# module_special_reg.net
KiCad netlist of a schematic drawn in EAGLE
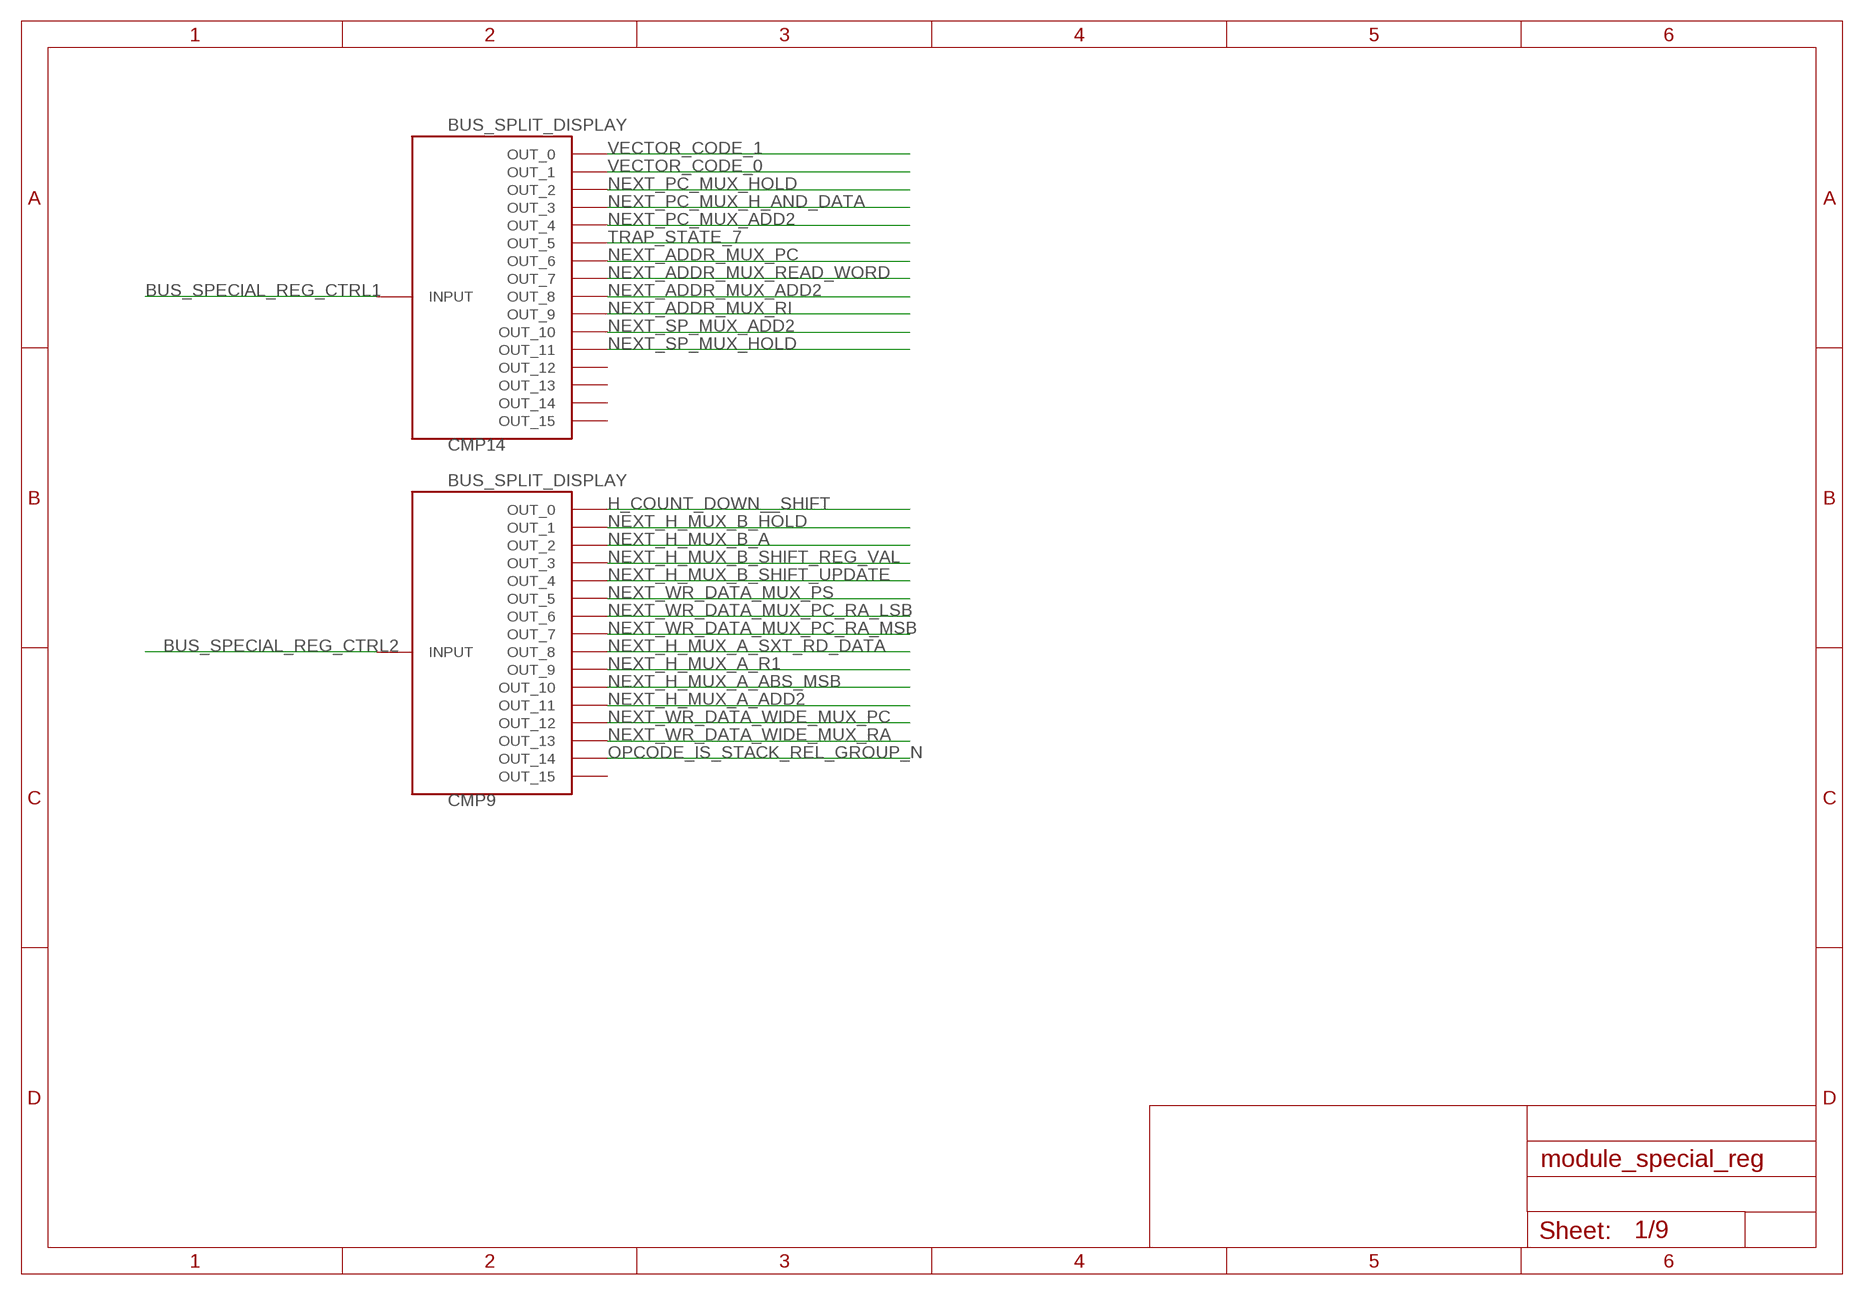
[diagram p0: schematic, sheet 1]
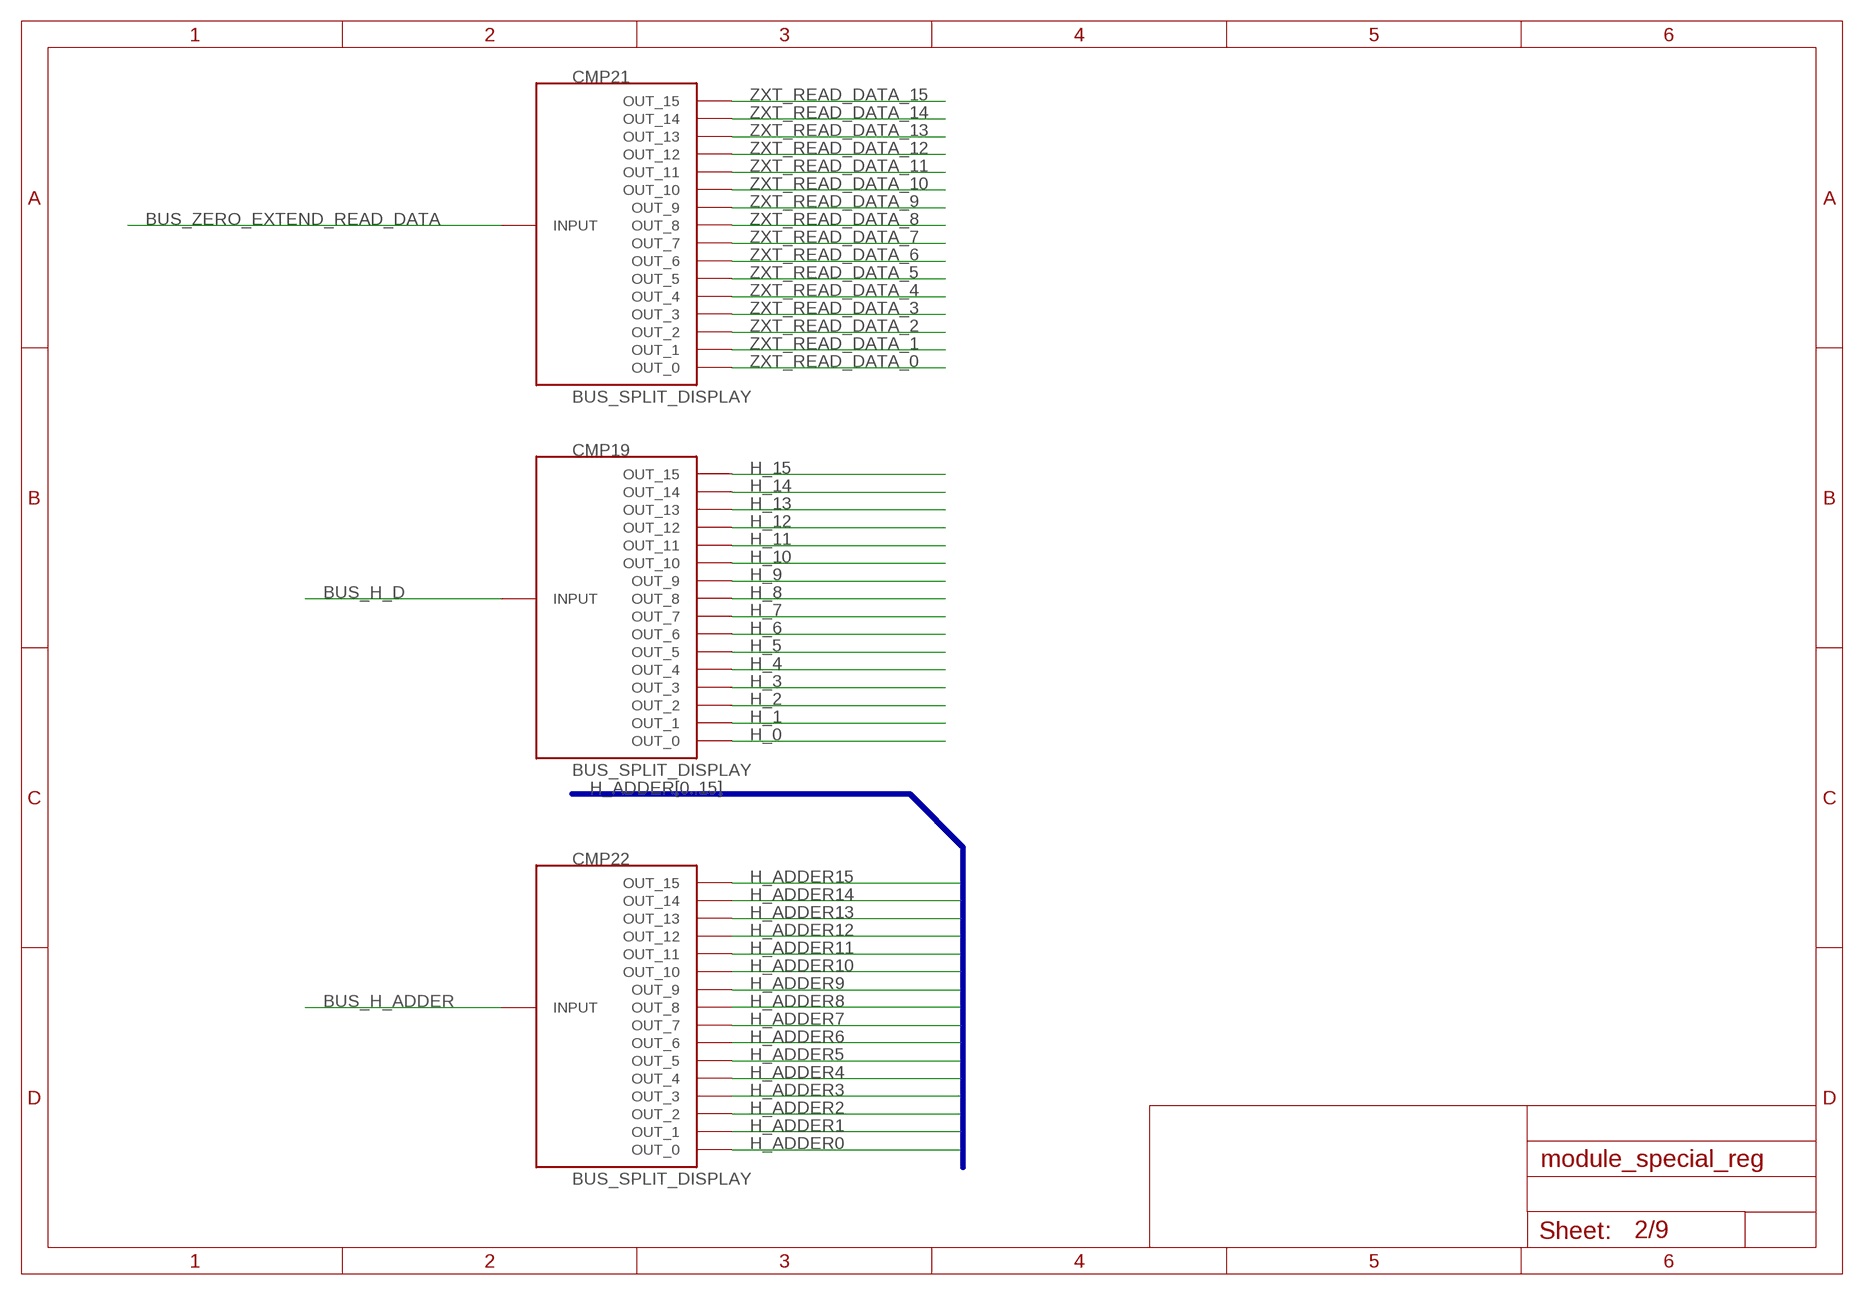
[diagram p1: schematic, sheet 2]
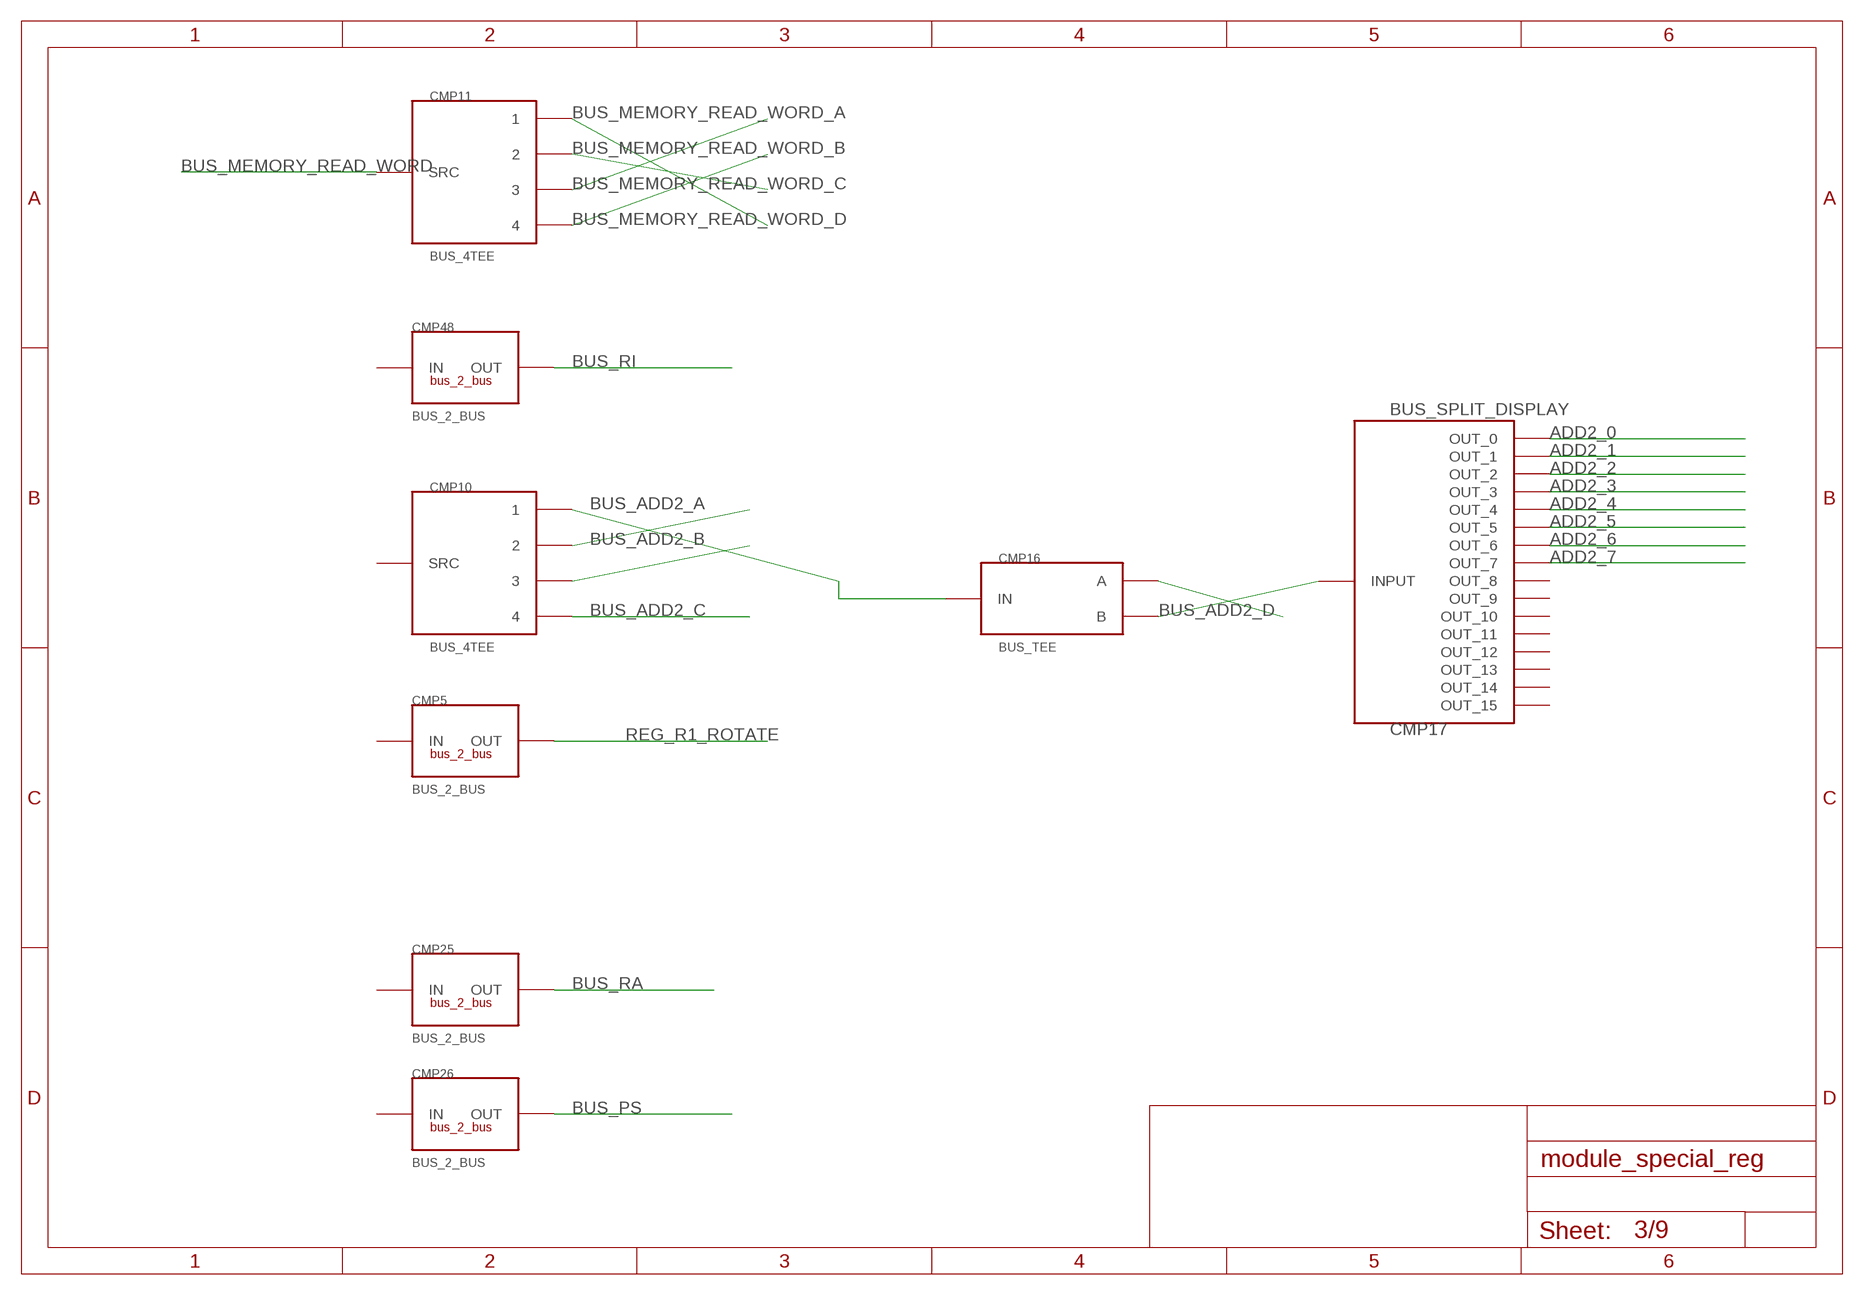
[diagram p2: schematic, sheet 3]
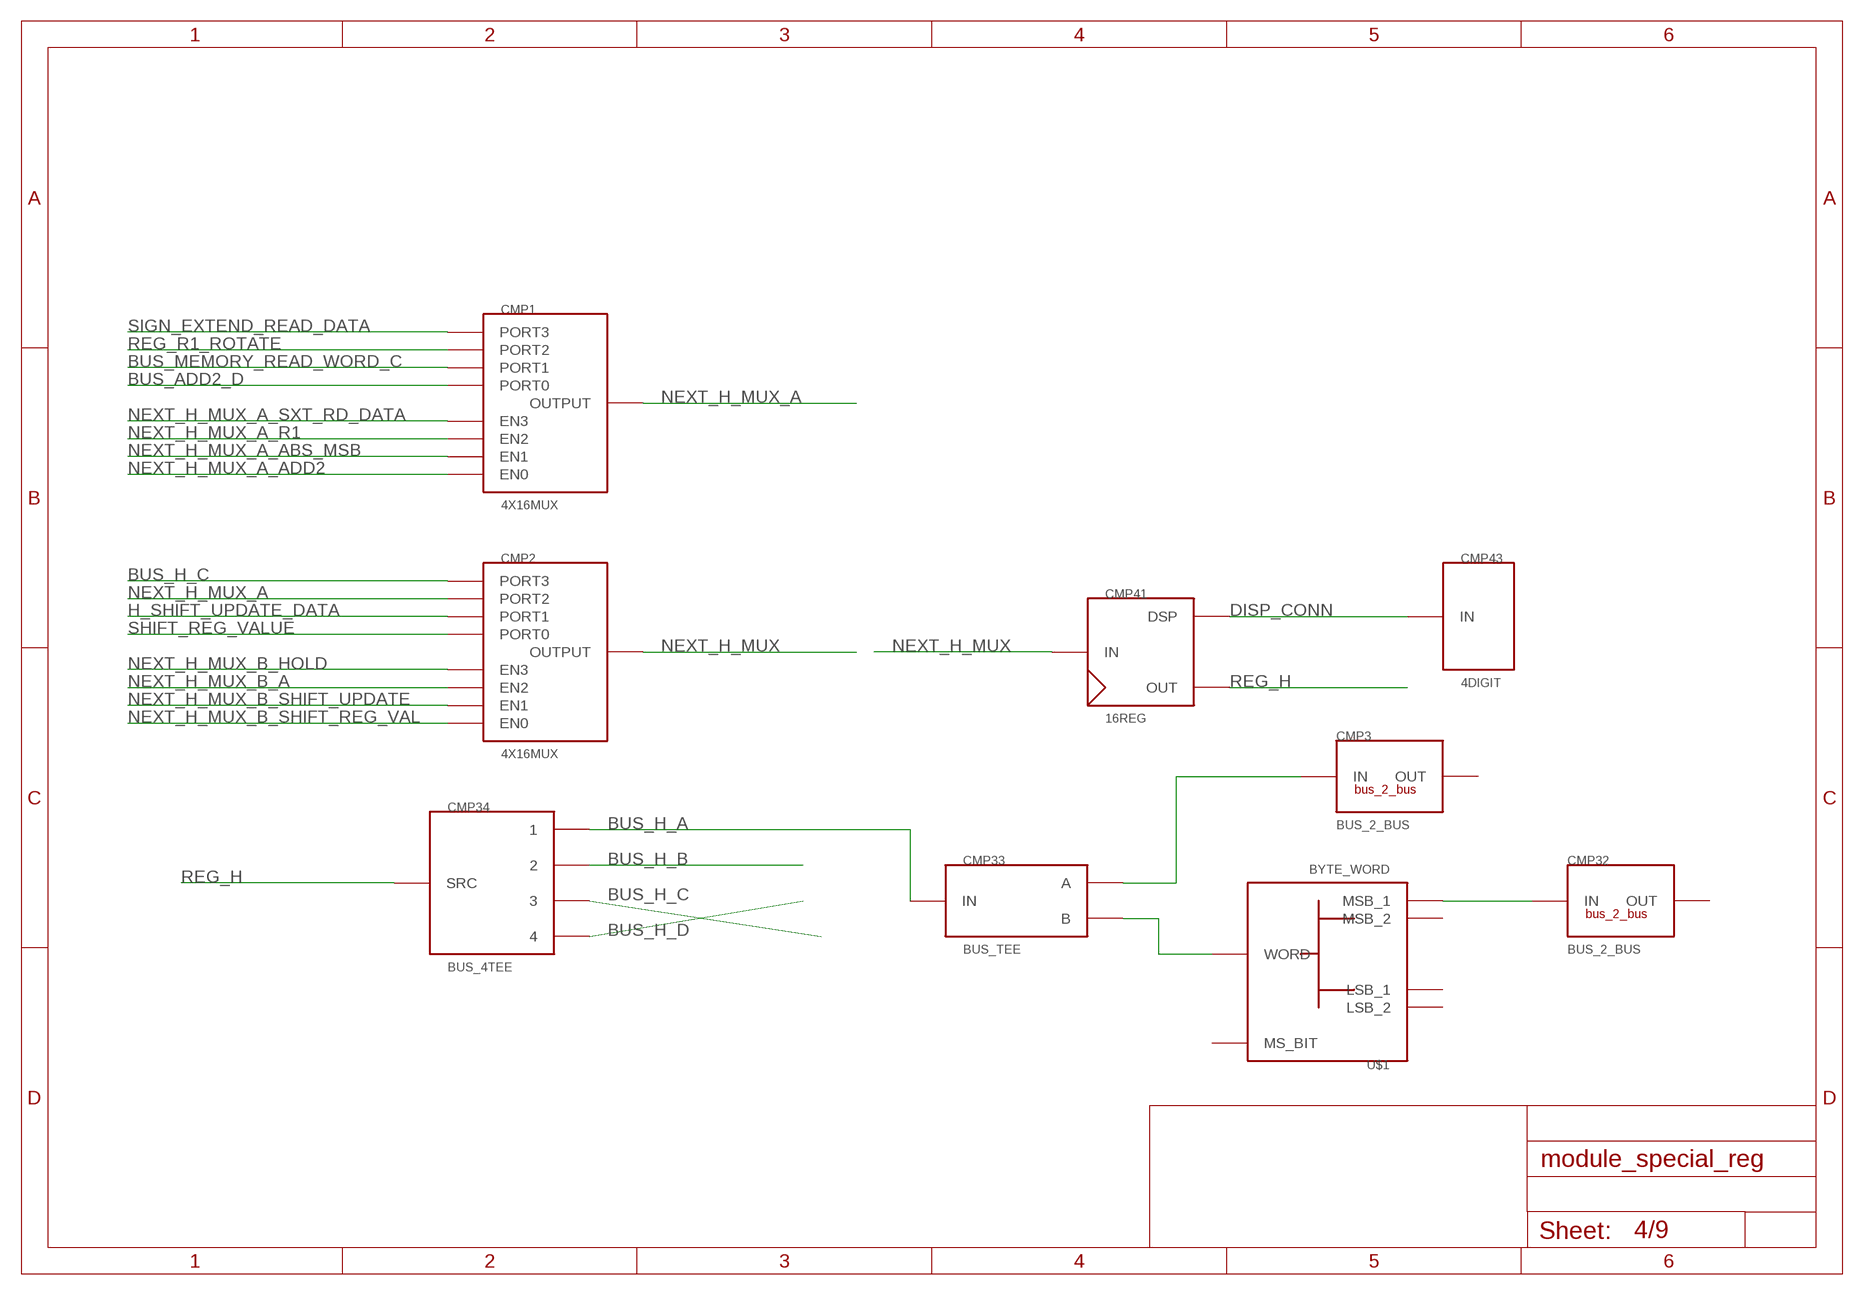
[diagram p3: schematic, sheet 4]
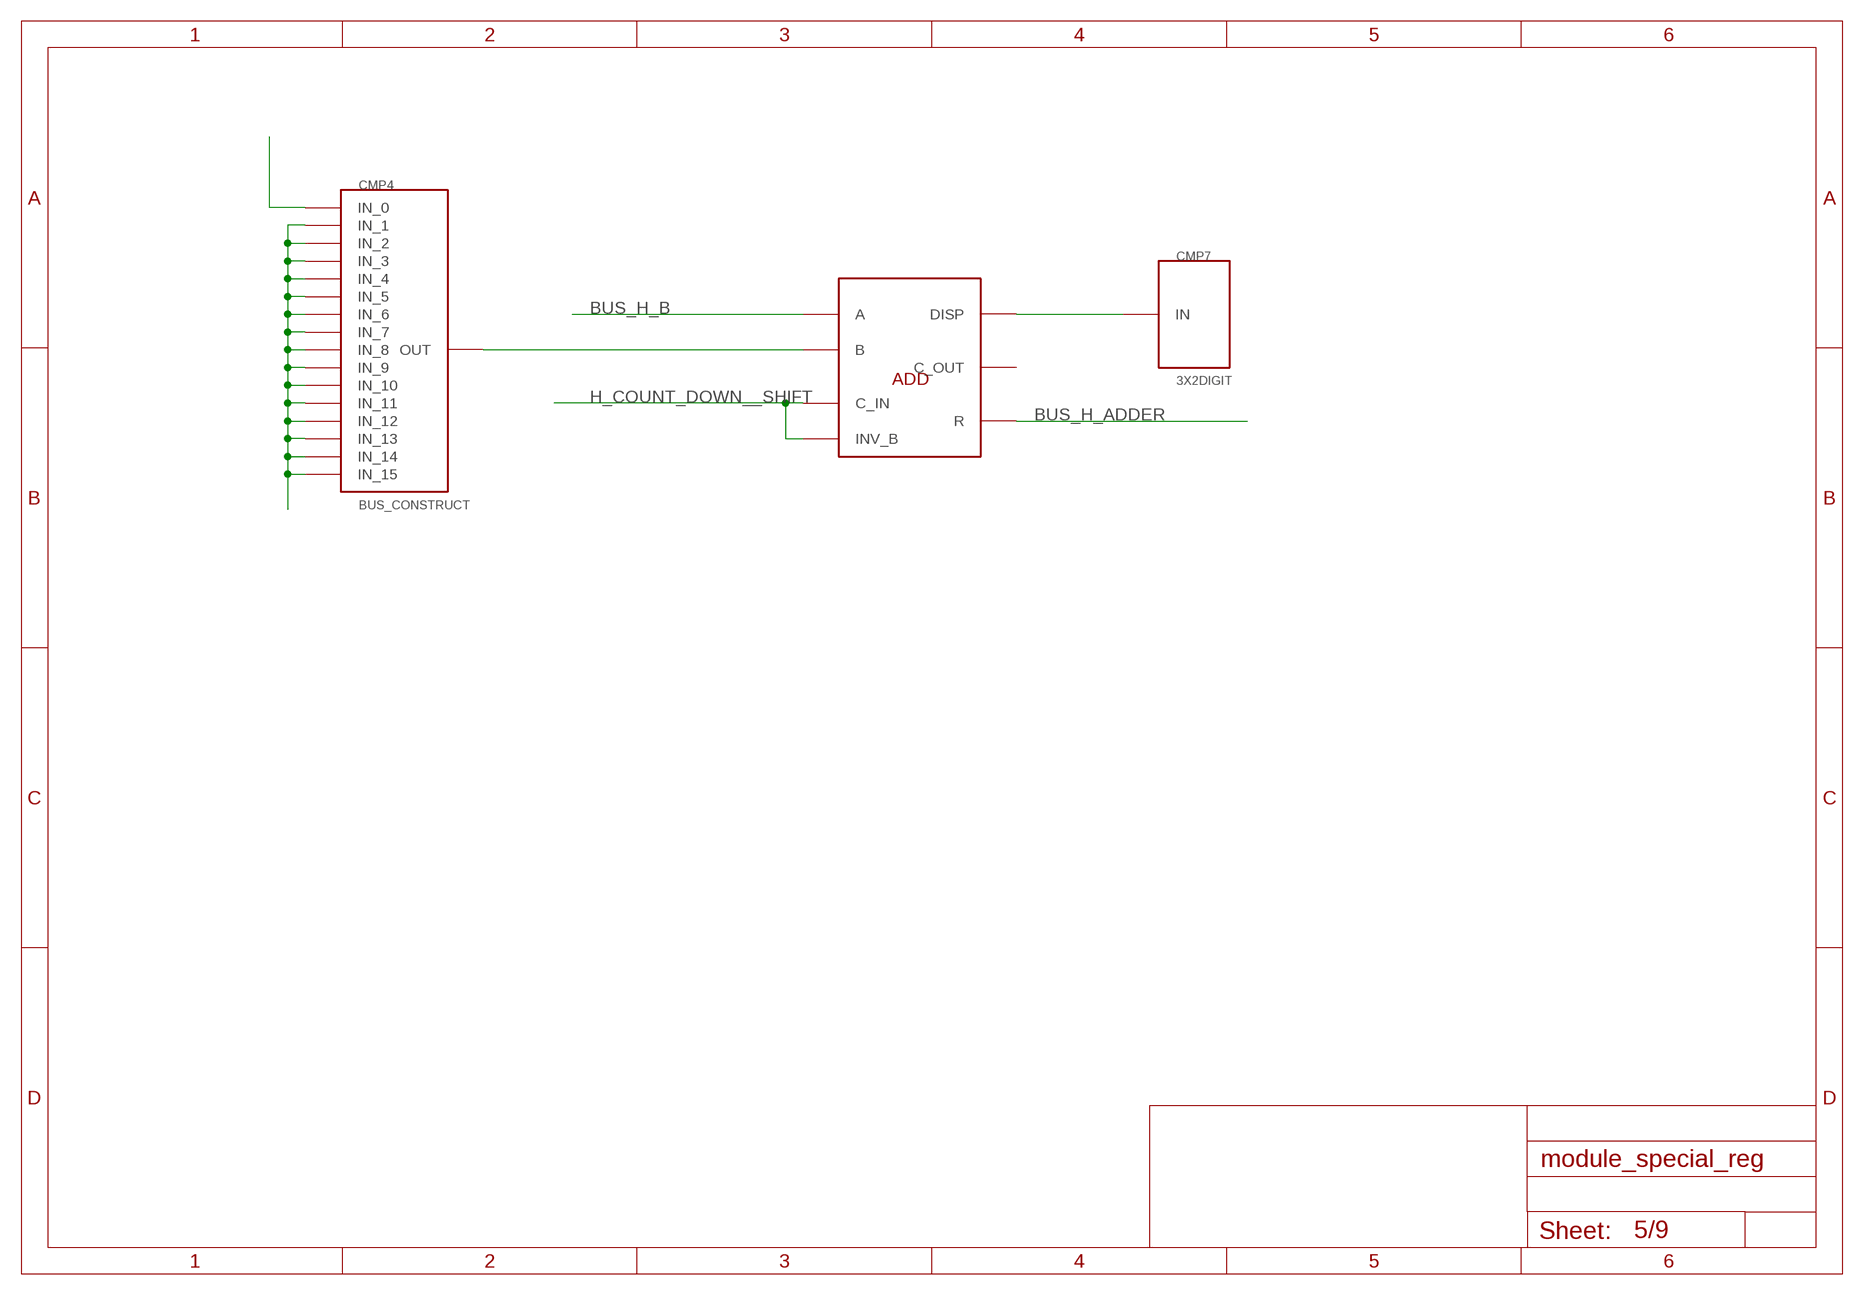
[diagram p4: schematic, sheet 5]
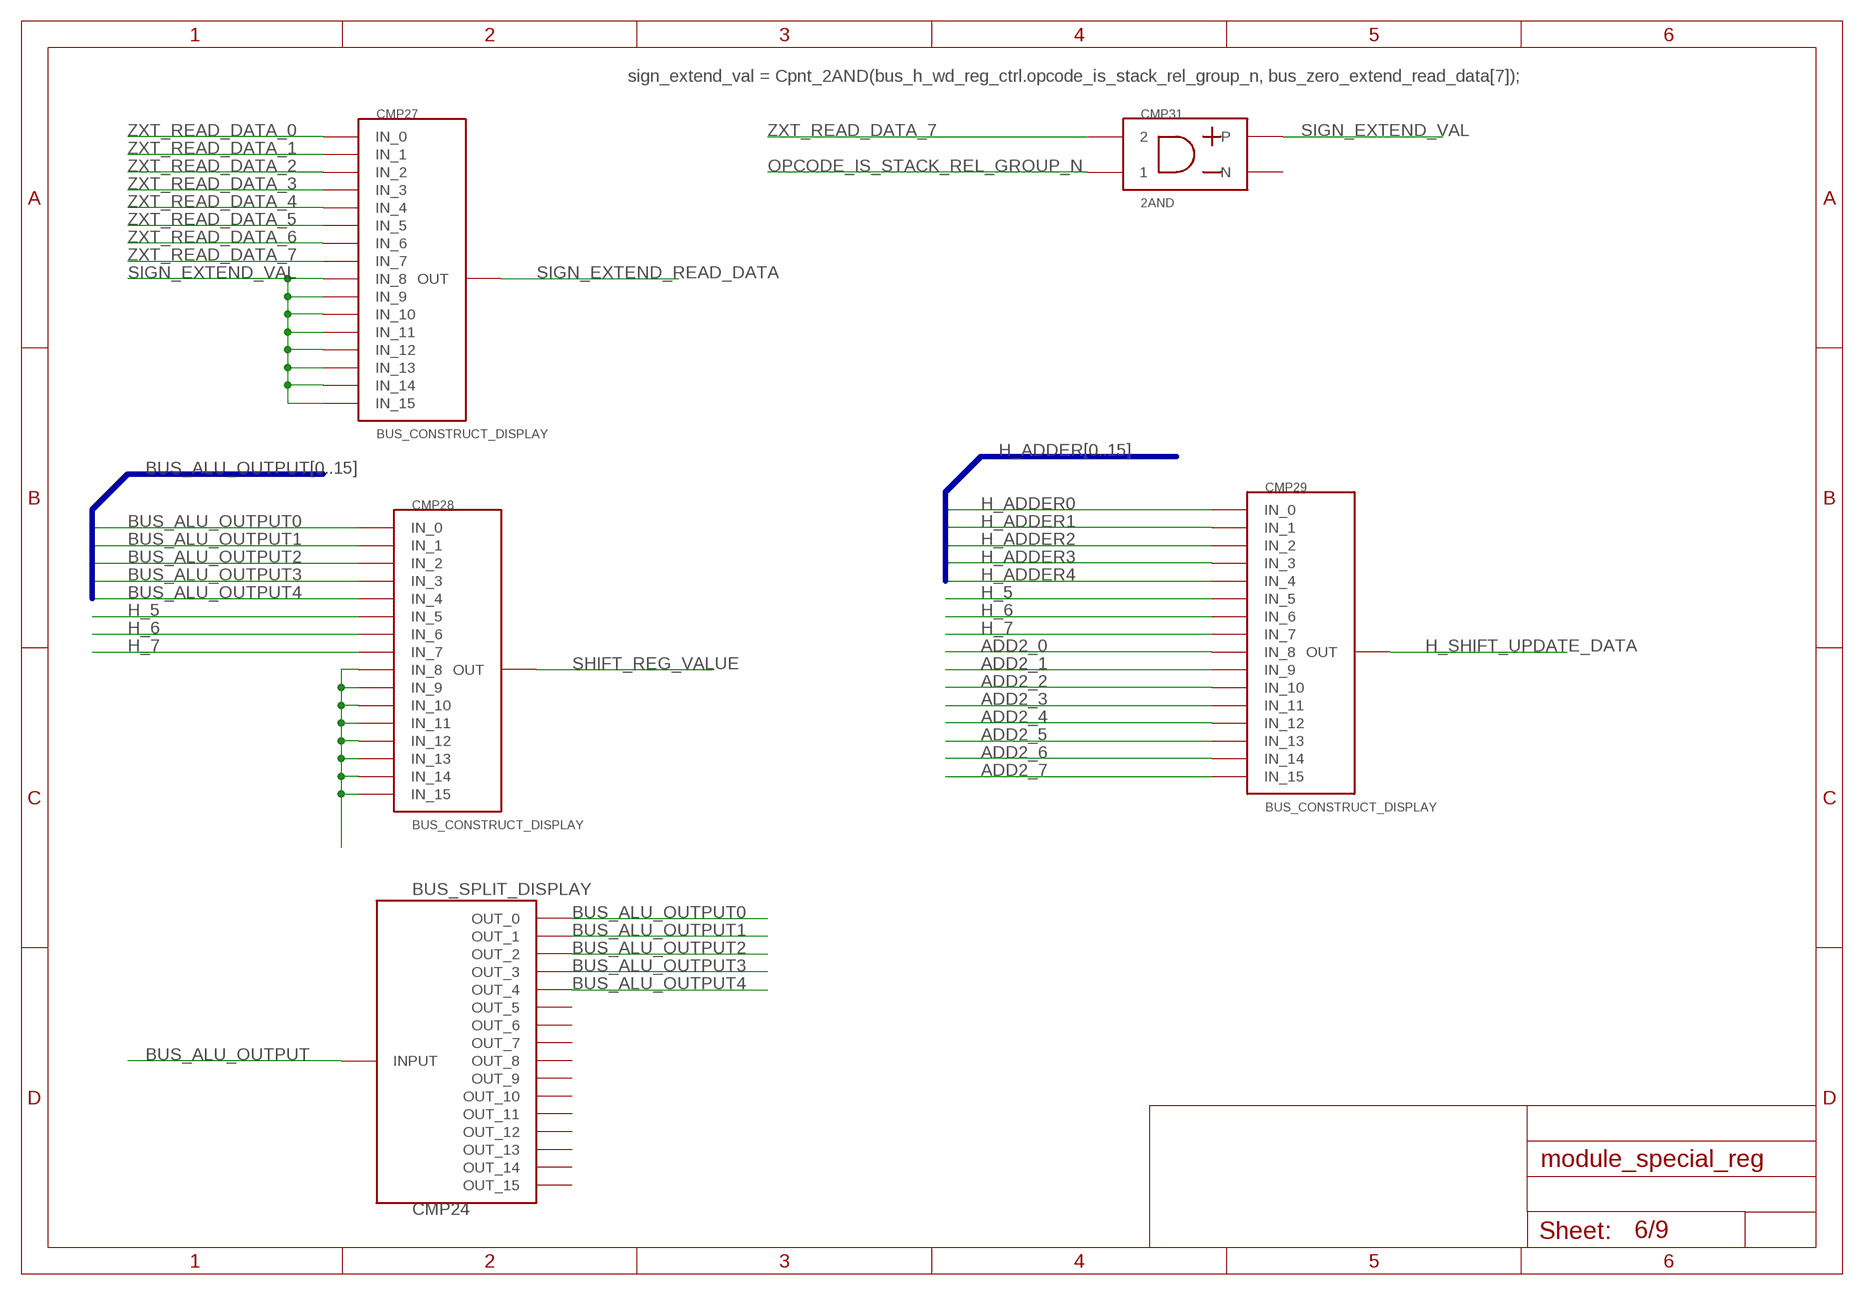
[diagram p5: schematic, sheet 6]
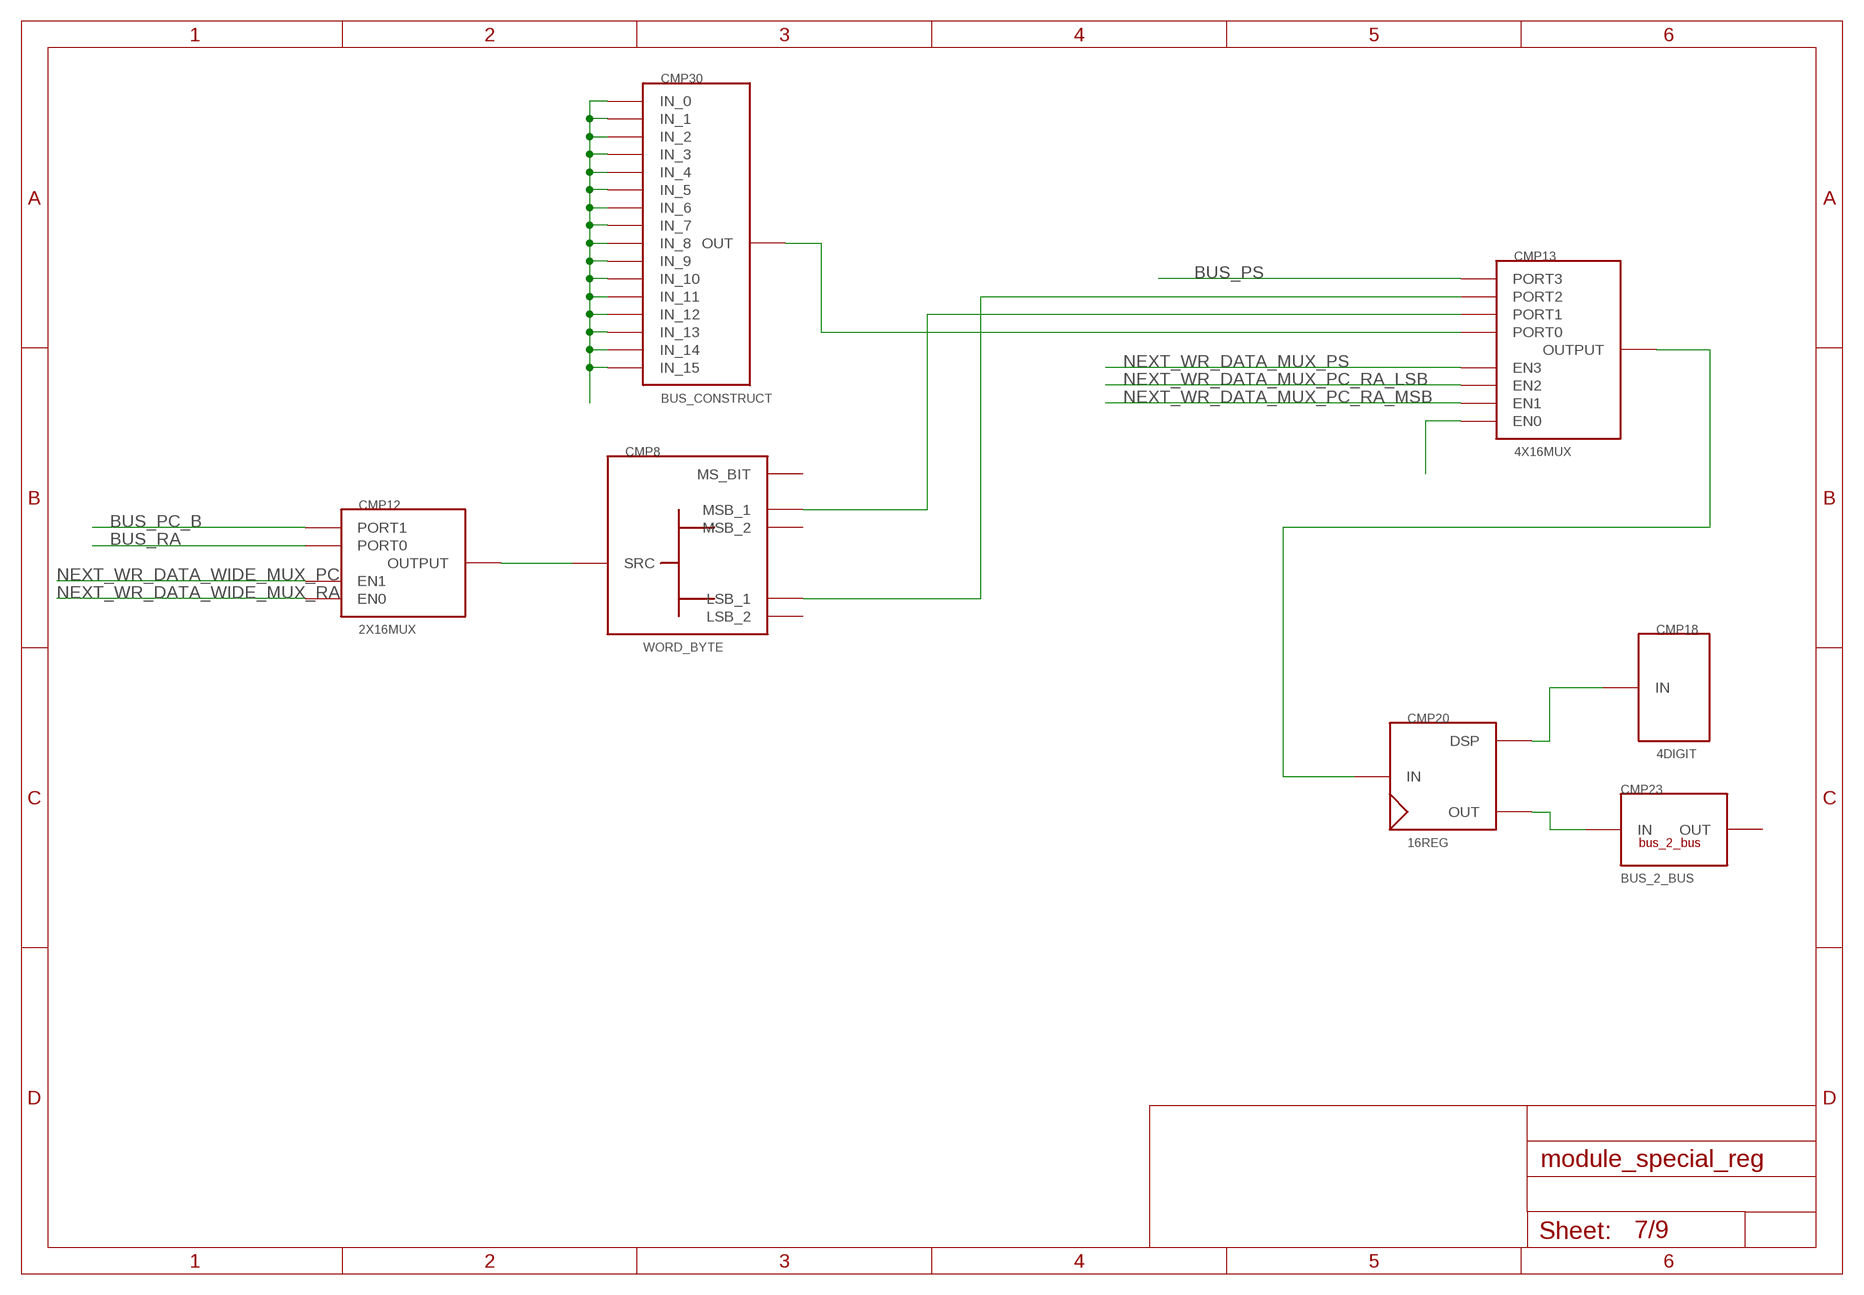
[diagram p6: schematic, sheet 7]
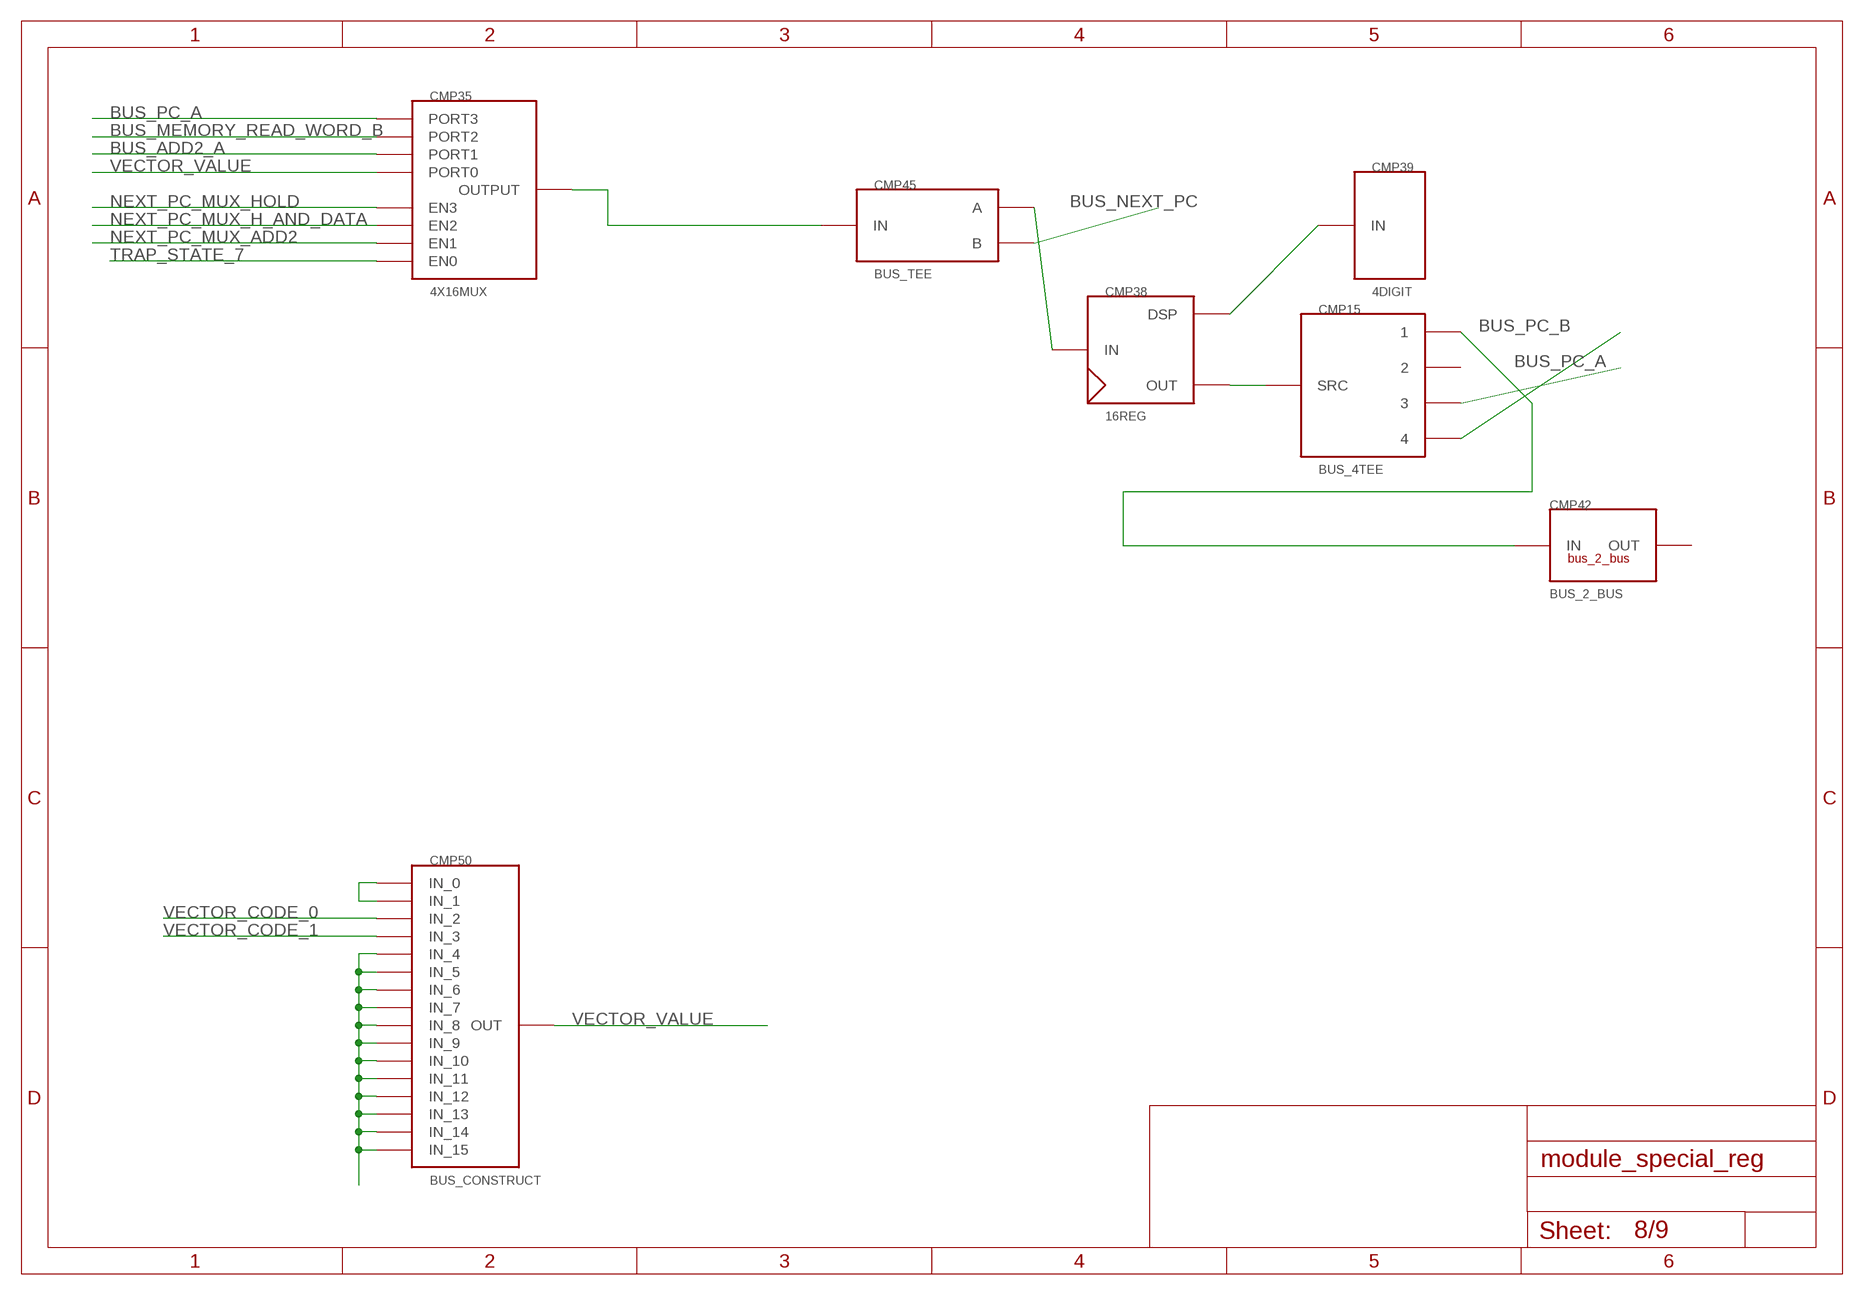
[diagram p7: schematic, sheet 8]
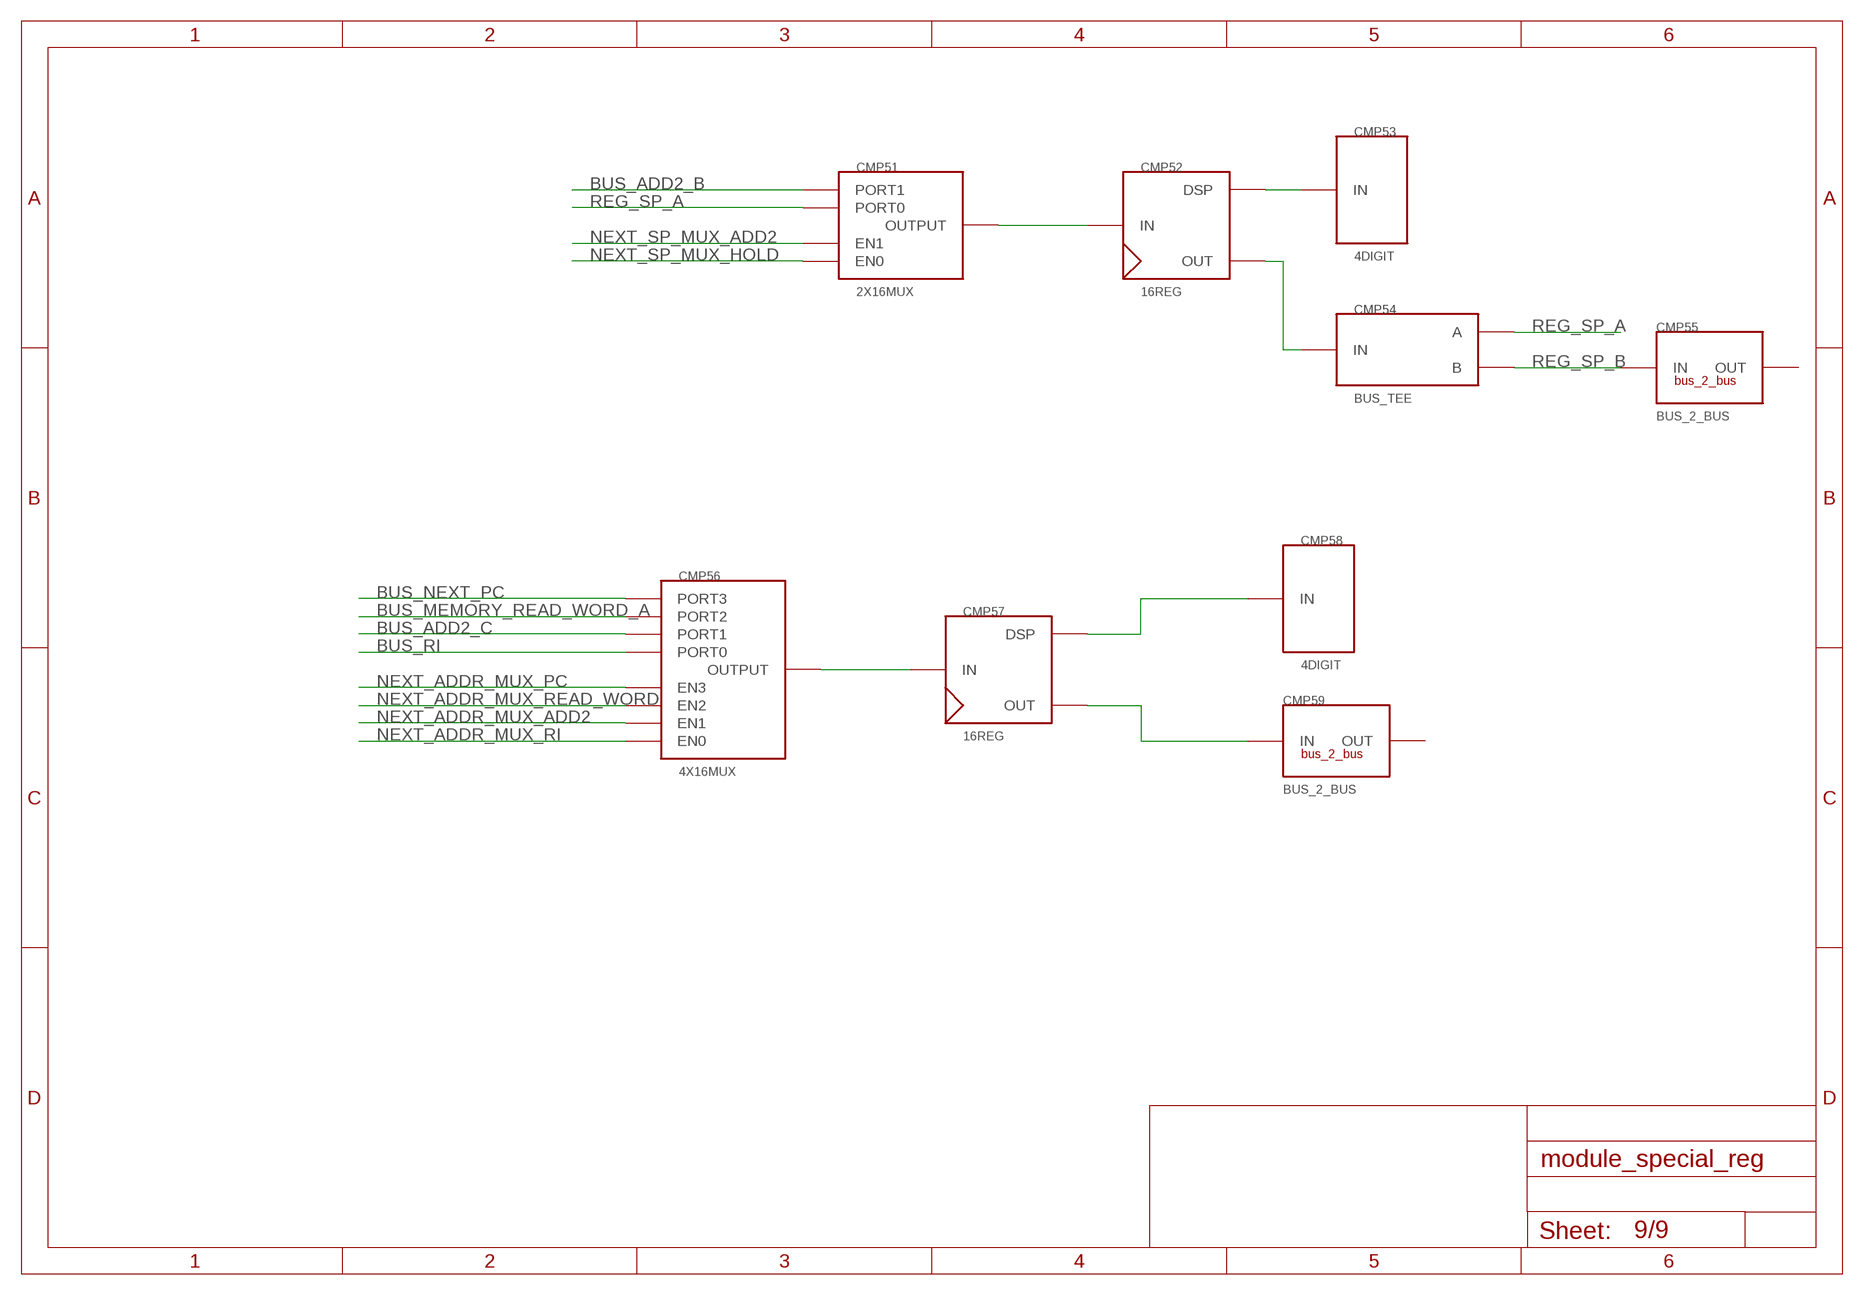
[diagram p8: schematic, sheet 9]

(export (version "E")
  (design (tool "Eeschema 10.0.6"))
  (components
    (comp (ref "CMP5")
      (value "BUS_2_BUS")
      (footprint "eagle-import:BUS2BUS")
      (libsource (lib "eagle-import") (part "BUS_2_BUS"))
    )
    (comp (ref "CMP10")
      (value "BUS_4TEE")
      (footprint "eagle-import:BUS_4TEE")
      (libsource (lib "eagle-import") (part "BUS_4TEE"))
    )
    (comp (ref "CMP11")
      (value "BUS_4TEE")
      (footprint "eagle-import:BUS_4TEE")
      (libsource (lib "eagle-import") (part "BUS_4TEE"))
    )
    (comp (ref "CMP16")
      (value "BUS_TEE")
      (footprint "eagle-import:BUS_TEE")
      (libsource (lib "eagle-import") (part "BUS_TEE"))
    )
    (comp (ref "CMP17")
      (value "BUS_SPLIT_DISPLAY")
      (footprint "eagle-import:BUS_SPLIT_DISPLAY")
      (libsource (lib "eagle-import") (part "BUS_SPLIT_DISPLAY"))
    )
    (comp (ref "CMP25")
      (value "BUS_2_BUS")
      (footprint "eagle-import:BUS2BUS")
      (libsource (lib "eagle-import") (part "BUS_2_BUS"))
    )
    (comp (ref "CMP26")
      (value "BUS_2_BUS")
      (footprint "eagle-import:BUS2BUS")
      (libsource (lib "eagle-import") (part "BUS_2_BUS"))
    )
    (comp (ref "CMP48")
      (value "BUS_2_BUS")
      (footprint "eagle-import:BUS2BUS")
      (libsource (lib "eagle-import") (part "BUS_2_BUS"))
    )
    (comp (ref "CMP1")
      (value "4X16MUX")
      (footprint "eagle-import:4X16MUX")
      (libsource (lib "eagle-import") (part "4X16MUX"))
    )
    (comp (ref "CMP2")
      (value "4X16MUX")
      (footprint "eagle-import:4X16MUX")
      (libsource (lib "eagle-import") (part "4X16MUX"))
    )
    (comp (ref "CMP3")
      (value "BUS_2_BUS")
      (footprint "eagle-import:BUS2BUS")
      (libsource (lib "eagle-import") (part "BUS_2_BUS"))
    )
    (comp (ref "CMP32")
      (value "BUS_2_BUS")
      (footprint "eagle-import:BUS2BUS")
      (libsource (lib "eagle-import") (part "BUS_2_BUS"))
    )
    (comp (ref "CMP33")
      (value "BUS_TEE")
      (footprint "eagle-import:BUS_TEE")
      (libsource (lib "eagle-import") (part "BUS_TEE"))
    )
    (comp (ref "CMP34")
      (value "BUS_4TEE")
      (footprint "eagle-import:BUS_4TEE")
      (libsource (lib "eagle-import") (part "BUS_4TEE"))
    )
    (comp (ref "CMP41")
      (value "16REG")
      (footprint "eagle-import:16REG")
      (libsource (lib "eagle-import") (part "16REG"))
    )
    (comp (ref "CMP43")
      (value "4DIGIT")
      (footprint "eagle-import:4DIGIT")
      (libsource (lib "eagle-import") (part "4DIGIT"))
    )
    (comp (ref "U$1")
      (value "BYTE_WORD")
      (footprint "eagle-import:WORD_BYTE")
      (libsource (lib "eagle-import") (part "BYTE_WORD"))
    )
    (comp (ref "CMP8")
      (value "WORD_BYTE")
      (footprint "eagle-import:WORD_BYTE")
      (libsource (lib "eagle-import") (part "WORD_BYTE"))
    )
    (comp (ref "CMP12")
      (value "2X16MUX")
      (footprint "eagle-import:2X16MUX")
      (libsource (lib "eagle-import") (part "2X16MUX"))
    )
    (comp (ref "CMP13")
      (value "4X16MUX")
      (footprint "eagle-import:4X16MUX")
      (libsource (lib "eagle-import") (part "4X16MUX"))
    )
    (comp (ref "CMP18")
      (value "4DIGIT")
      (footprint "eagle-import:4DIGIT")
      (libsource (lib "eagle-import") (part "4DIGIT"))
    )
    (comp (ref "CMP20")
      (value "16REG")
      (footprint "eagle-import:16REG")
      (libsource (lib "eagle-import") (part "16REG"))
    )
    (comp (ref "CMP23")
      (value "BUS_2_BUS")
      (footprint "eagle-import:BUS2BUS")
      (libsource (lib "eagle-import") (part "BUS_2_BUS"))
    )
    (comp (ref "CMP30")
      (value "BUS_CONSTRUCT")
      (footprint "eagle-import:BUS_SPLIT")
      (libsource (lib "eagle-import") (part "BUS_CONSTRUCT"))
    )
    (comp (ref "CMP19")
      (value "BUS_SPLIT_DISPLAY")
      (footprint "eagle-import:BUS_SPLIT_DISPLAY")
      (libsource (lib "eagle-import") (part "BUS_SPLIT_DISPLAY"))
    )
    (comp (ref "CMP21")
      (value "BUS_SPLIT_DISPLAY")
      (footprint "eagle-import:BUS_SPLIT_DISPLAY")
      (libsource (lib "eagle-import") (part "BUS_SPLIT_DISPLAY"))
    )
    (comp (ref "CMP22")
      (value "BUS_SPLIT_DISPLAY")
      (footprint "eagle-import:BUS_SPLIT_DISPLAY")
      (libsource (lib "eagle-import") (part "BUS_SPLIT_DISPLAY"))
    )
    (comp (ref "CMP15")
      (value "BUS_4TEE")
      (footprint "eagle-import:BUS_4TEE")
      (libsource (lib "eagle-import") (part "BUS_4TEE"))
    )
    (comp (ref "CMP35")
      (value "4X16MUX")
      (footprint "eagle-import:4X16MUX")
      (libsource (lib "eagle-import") (part "4X16MUX"))
    )
    (comp (ref "CMP38")
      (value "16REG")
      (footprint "eagle-import:16REG")
      (libsource (lib "eagle-import") (part "16REG"))
    )
    (comp (ref "CMP39")
      (value "4DIGIT")
      (footprint "eagle-import:4DIGIT")
      (libsource (lib "eagle-import") (part "4DIGIT"))
    )
    (comp (ref "CMP42")
      (value "BUS_2_BUS")
      (footprint "eagle-import:BUS2BUS")
      (libsource (lib "eagle-import") (part "BUS_2_BUS"))
    )
    (comp (ref "CMP45")
      (value "BUS_TEE")
      (footprint "eagle-import:BUS_TEE")
      (libsource (lib "eagle-import") (part "BUS_TEE"))
    )
    (comp (ref "CMP50")
      (value "BUS_CONSTRUCT")
      (footprint "eagle-import:BUS_SPLIT")
      (libsource (lib "eagle-import") (part "BUS_CONSTRUCT"))
    )
    (comp (ref "CMP24")
      (value "BUS_SPLIT_DISPLAY")
      (footprint "eagle-import:BUS_SPLIT_DISPLAY")
      (libsource (lib "eagle-import") (part "BUS_SPLIT_DISPLAY"))
    )
    (comp (ref "CMP27")
      (value "BUS_CONSTRUCT_DISPLAY")
      (footprint "eagle-import:BUS_SPLIT_DISPLAY")
      (libsource (lib "eagle-import") (part "BUS_CONSTRUCT_DISPLAY"))
    )
    (comp (ref "CMP28")
      (value "BUS_CONSTRUCT_DISPLAY")
      (footprint "eagle-import:BUS_SPLIT_DISPLAY")
      (libsource (lib "eagle-import") (part "BUS_CONSTRUCT_DISPLAY"))
    )
    (comp (ref "CMP29")
      (value "BUS_CONSTRUCT_DISPLAY")
      (footprint "eagle-import:BUS_SPLIT_DISPLAY")
      (libsource (lib "eagle-import") (part "BUS_CONSTRUCT_DISPLAY"))
    )
    (comp (ref "CMP31")
      (value "2AND")
      (footprint "eagle-import:2AND")
      (libsource (lib "eagle-import") (part "2AND"))
    )
    (comp (ref "CMP9")
      (value "BUS_SPLIT_DISPLAY")
      (footprint "eagle-import:BUS_SPLIT_DISPLAY")
      (libsource (lib "eagle-import") (part "BUS_SPLIT_DISPLAY"))
    )
    (comp (ref "CMP14")
      (value "BUS_SPLIT_DISPLAY")
      (footprint "eagle-import:BUS_SPLIT_DISPLAY")
      (libsource (lib "eagle-import") (part "BUS_SPLIT_DISPLAY"))
    )
    (comp (ref "CMP51")
      (value "2X16MUX")
      (footprint "eagle-import:2X16MUX")
      (libsource (lib "eagle-import") (part "2X16MUX"))
    )
    (comp (ref "CMP52")
      (value "16REG")
      (footprint "eagle-import:16REG")
      (libsource (lib "eagle-import") (part "16REG"))
    )
    (comp (ref "CMP53")
      (value "4DIGIT")
      (footprint "eagle-import:4DIGIT")
      (libsource (lib "eagle-import") (part "4DIGIT"))
    )
    (comp (ref "CMP54")
      (value "BUS_TEE")
      (footprint "eagle-import:BUS_TEE")
      (libsource (lib "eagle-import") (part "BUS_TEE"))
    )
    (comp (ref "CMP55")
      (value "BUS_2_BUS")
      (footprint "eagle-import:BUS2BUS")
      (libsource (lib "eagle-import") (part "BUS_2_BUS"))
    )
    (comp (ref "CMP56")
      (value "4X16MUX")
      (footprint "eagle-import:4X16MUX")
      (libsource (lib "eagle-import") (part "4X16MUX"))
    )
    (comp (ref "CMP57")
      (value "16REG")
      (footprint "eagle-import:16REG")
      (libsource (lib "eagle-import") (part "16REG"))
    )
    (comp (ref "CMP58")
      (value "4DIGIT")
      (footprint "eagle-import:4DIGIT")
      (libsource (lib "eagle-import") (part "4DIGIT"))
    )
    (comp (ref "CMP59")
      (value "BUS_2_BUS")
      (footprint "eagle-import:BUS2BUS")
      (libsource (lib "eagle-import") (part "BUS_2_BUS"))
    )
    (comp (ref "CMP4")
      (value "BUS_CONSTRUCT")
      (footprint "eagle-import:BUS_SPLIT")
      (libsource (lib "eagle-import") (part "BUS_CONSTRUCT"))
    )
    (comp (ref "CMP6")
      (value "8BIT_ADD_SUB")
      (footprint "eagle-import:8BIT_ADD_SUB")
      (libsource (lib "eagle-import") (part "8BIT_ADD_SUB"))
    )
    (comp (ref "CMP7")
      (value "3X2DIGIT")
      (footprint "eagle-import:3X2DIGIT")
      (libsource (lib "eagle-import") (part "3X2DIGIT"))
    )
  )
  (nets
    (net (code "26") (name "ADD2_0") (class "Default")
      (node (ref "CMP17") (pin "P$1") (pinfunction "OUT_0_P$1") (pintype "output"))
      (node (ref "CMP29") (pin "P$9") (pinfunction "IN_8_P$9") (pintype "input"))
    )
    (net (code "27") (name "ADD2_1") (class "Default")
      (node (ref "CMP17") (pin "P$2") (pinfunction "OUT_1_P$2") (pintype "output"))
      (node (ref "CMP29") (pin "P$10") (pinfunction "IN_9_P$10") (pintype "input"))
    )
    (net (code "28") (name "ADD2_2") (class "Default")
      (node (ref "CMP17") (pin "P$3") (pinfunction "OUT_2_P$3") (pintype "output"))
      (node (ref "CMP29") (pin "P$11") (pinfunction "IN_10_P$11") (pintype "input"))
    )
    (net (code "29") (name "ADD2_3") (class "Default")
      (node (ref "CMP17") (pin "P$4") (pinfunction "OUT_3_P$4") (pintype "output"))
      (node (ref "CMP29") (pin "P$12") (pinfunction "IN_11_P$12") (pintype "input"))
    )
    (net (code "30") (name "ADD2_4") (class "Default")
      (node (ref "CMP17") (pin "P$5") (pinfunction "OUT_4_P$5") (pintype "output"))
      (node (ref "CMP29") (pin "P$13") (pinfunction "IN_12_P$13") (pintype "input"))
    )
    (net (code "31") (name "ADD2_5") (class "Default")
      (node (ref "CMP17") (pin "P$6") (pinfunction "OUT_5_P$6") (pintype "output"))
      (node (ref "CMP29") (pin "P$14") (pinfunction "IN_13_P$14") (pintype "input"))
    )
    (net (code "32") (name "ADD2_6") (class "Default")
      (node (ref "CMP17") (pin "P$7") (pinfunction "OUT_6_P$7") (pintype "output"))
      (node (ref "CMP29") (pin "P$15") (pinfunction "IN_14_P$15") (pintype "input"))
    )
    (net (code "33") (name "ADD2_7") (class "Default")
      (node (ref "CMP17") (pin "P$8") (pinfunction "OUT_7_P$8") (pintype "output"))
      (node (ref "CMP29") (pin "P$16") (pinfunction "IN_15_P$16") (pintype "input"))
    )
    (net (code "34") (name "BUS_ADD2_A") (class "Default")
      (node (ref "CMP10") (pin "2") (pinfunction "2_2") (pintype "output"))
      (node (ref "CMP35") (pin "PORT1") (pinfunction "PORT1_PORT1") (pintype "input"))
    )
    (net (code "35") (name "BUS_ADD2_B") (class "Default")
      (node (ref "CMP10") (pin "3") (pinfunction "3_3") (pintype "output"))
      (node (ref "CMP51") (pin "PORT1") (pinfunction "PORT1_PORT1") (pintype "input"))
    )
    (net (code "36") (name "BUS_ADD2_C") (class "Default")
      (node (ref "CMP10") (pin "4") (pinfunction "4_4") (pintype "output"))
      (node (ref "CMP56") (pin "PORT1") (pinfunction "PORT1_PORT1") (pintype "input"))
    )
    (net (code "37") (name "BUS_ADD2_D") (class "Default")
      (node (ref "CMP1") (pin "PORT0") (pinfunction "PORT0_PORT0") (pintype "input"))
      (node (ref "CMP16") (pin "OUT_A") (pinfunction "A_OUT_A") (pintype "output"))
    )
    (net (code "38") (name "BUS_ALU_OUTPUT") (class "Default")
      (node (ref "CMP24") (pin "INPUT") (pinfunction "INPUT_INPUT") (pintype "input"))
    )
    (net (code "39") (name "BUS_ALU_OUTPUT0") (class "Default")
      (node (ref "CMP24") (pin "P$1") (pinfunction "OUT_0_P$1") (pintype "output"))
      (node (ref "CMP28") (pin "P$1") (pinfunction "IN_0_P$1") (pintype "input"))
    )
    (net (code "40") (name "BUS_ALU_OUTPUT1") (class "Default")
      (node (ref "CMP24") (pin "P$2") (pinfunction "OUT_1_P$2") (pintype "output"))
      (node (ref "CMP28") (pin "P$2") (pinfunction "IN_1_P$2") (pintype "input"))
    )
    (net (code "41") (name "BUS_ALU_OUTPUT2") (class "Default")
      (node (ref "CMP24") (pin "P$3") (pinfunction "OUT_2_P$3") (pintype "output"))
      (node (ref "CMP28") (pin "P$3") (pinfunction "IN_2_P$3") (pintype "input"))
    )
    (net (code "42") (name "BUS_ALU_OUTPUT3") (class "Default")
      (node (ref "CMP24") (pin "P$4") (pinfunction "OUT_3_P$4") (pintype "output"))
      (node (ref "CMP28") (pin "P$4") (pinfunction "IN_3_P$4") (pintype "input"))
    )
    (net (code "43") (name "BUS_ALU_OUTPUT4") (class "Default")
      (node (ref "CMP24") (pin "P$5") (pinfunction "OUT_4_P$5") (pintype "output"))
      (node (ref "CMP28") (pin "P$5") (pinfunction "IN_4_P$5") (pintype "input"))
    )
    (net (code "44") (name "BUS_H_A") (class "Default")
      (node (ref "CMP33") (pin "INPUT") (pinfunction "IN_INPUT") (pintype "input"))
      (node (ref "CMP34") (pin "1") (pinfunction "1_1") (pintype "output"))
    )
    (net (code "45") (name "BUS_H_ADDER") (class "Default")
      (node (ref "CMP22") (pin "INPUT") (pinfunction "INPUT_INPUT") (pintype "input"))
      (node (ref "CMP6") (pin "R") (pinfunction "R_R") (pintype "output"))
    )
    (net (code "46") (name "BUS_H_B") (class "Default")
      (node (ref "CMP34") (pin "2") (pinfunction "2_2") (pintype "output"))
      (node (ref "CMP6") (pin "A") (pinfunction "A_A") (pintype "input"))
    )
    (net (code "47") (name "BUS_H_C") (class "Default")
      (node (ref "CMP2") (pin "PORT3") (pinfunction "PORT3_PORT3") (pintype "input"))
      (node (ref "CMP34") (pin "4") (pinfunction "4_4") (pintype "output"))
    )
    (net (code "48") (name "BUS_H_D") (class "Default")
      (node (ref "CMP19") (pin "INPUT") (pinfunction "INPUT_INPUT") (pintype "input"))
      (node (ref "CMP34") (pin "3") (pinfunction "3_3") (pintype "output"))
    )
    (net (code "49") (name "BUS_MEMORY_READ_WORD") (class "Default")
      (node (ref "CMP11") (pin "SRC") (pinfunction "SRC_SRC") (pintype "input"))
    )
    (net (code "50") (name "BUS_MEMORY_READ_WORD_A") (class "Default")
      (node (ref "CMP11") (pin "3") (pinfunction "3_3") (pintype "output"))
      (node (ref "CMP56") (pin "PORT2") (pinfunction "PORT2_PORT2") (pintype "input"))
    )
    (net (code "51") (name "BUS_MEMORY_READ_WORD_B") (class "Default")
      (node (ref "CMP11") (pin "4") (pinfunction "4_4") (pintype "output"))
      (node (ref "CMP35") (pin "PORT2") (pinfunction "PORT2_PORT2") (pintype "input"))
    )
    (net (code "52") (name "BUS_MEMORY_READ_WORD_C") (class "Default")
      (node (ref "CMP1") (pin "PORT1") (pinfunction "PORT1_PORT1") (pintype "input"))
      (node (ref "CMP11") (pin "2") (pinfunction "2_2") (pintype "output"))
    )
    (net (code "53") (name "BUS_MEMORY_READ_WORD_D") (class "Default")
      (node (ref "CMP11") (pin "1") (pinfunction "1_1") (pintype "output"))
    )
    (net (code "54") (name "BUS_NEXT_PC") (class "Default")
      (node (ref "CMP45") (pin "OUTB") (pinfunction "B_OUTB") (pintype "output"))
      (node (ref "CMP56") (pin "PORT3") (pinfunction "PORT3_PORT3") (pintype "input"))
    )
    (net (code "55") (name "BUS_PC_A") (class "Default")
      (node (ref "CMP15") (pin "3") (pinfunction "3_3") (pintype "output"))
      (node (ref "CMP35") (pin "PORT3") (pinfunction "PORT3_PORT3") (pintype "input"))
    )
    (net (code "56") (name "BUS_PC_B") (class "Default")
      (node (ref "CMP12") (pin "PORT1") (pinfunction "PORT1_PORT1") (pintype "input"))
      (node (ref "CMP15") (pin "4") (pinfunction "4_4") (pintype "output"))
    )
    (net (code "57") (name "BUS_PS") (class "Default")
      (node (ref "CMP13") (pin "PORT3") (pinfunction "PORT3_PORT3") (pintype "input"))
      (node (ref "CMP26") (pin "P$2") (pinfunction "OUT_P$2") (pintype "output"))
    )
    (net (code "58") (name "BUS_RA") (class "Default")
      (node (ref "CMP12") (pin "PORT0") (pinfunction "PORT0_PORT0") (pintype "input"))
      (node (ref "CMP25") (pin "P$2") (pinfunction "OUT_P$2") (pintype "output"))
    )
    (net (code "59") (name "BUS_RI") (class "Default")
      (node (ref "CMP48") (pin "P$2") (pinfunction "OUT_P$2") (pintype "output"))
      (node (ref "CMP56") (pin "PORT0") (pinfunction "PORT0_PORT0") (pintype "input"))
    )
    (net (code "60") (name "BUS_SPECIAL_REG_CTRL1") (class "Default")
      (node (ref "CMP14") (pin "INPUT") (pinfunction "INPUT_INPUT") (pintype "input"))
    )
    (net (code "61") (name "BUS_SPECIAL_REG_CTRL2") (class "Default")
      (node (ref "CMP9") (pin "INPUT") (pinfunction "INPUT_INPUT") (pintype "input"))
    )
    (net (code "62") (name "BUS_ZERO_EXTEND_READ_DATA") (class "Default")
      (node (ref "CMP21") (pin "INPUT") (pinfunction "INPUT_INPUT") (pintype "input"))
    )
    (net (code "63") (name "DISP_CONN") (class "Default")
      (node (ref "CMP41") (pin "DISPLAY") (pinfunction "DSP_DISPLAY") (pintype "output"))
      (node (ref "CMP43") (pin "P$1") (pinfunction "IN_P$1") (pintype "input"))
    )
    (net (code "64") (name "H_0") (class "Default")
      (node (ref "CMP19") (pin "P$1") (pinfunction "OUT_0_P$1") (pintype "output"))
    )
    (net (code "65") (name "H_1") (class "Default")
      (node (ref "CMP19") (pin "P$2") (pinfunction "OUT_1_P$2") (pintype "output"))
    )
    (net (code "66") (name "H_2") (class "Default")
      (node (ref "CMP19") (pin "P$3") (pinfunction "OUT_2_P$3") (pintype "output"))
    )
    (net (code "67") (name "H_3") (class "Default")
      (node (ref "CMP19") (pin "P$4") (pinfunction "OUT_3_P$4") (pintype "output"))
    )
    (net (code "68") (name "H_4") (class "Default")
      (node (ref "CMP19") (pin "P$5") (pinfunction "OUT_4_P$5") (pintype "output"))
    )
    (net (code "69") (name "H_5") (class "Default")
      (node (ref "CMP19") (pin "P$6") (pinfunction "OUT_5_P$6") (pintype "output"))
      (node (ref "CMP28") (pin "P$6") (pinfunction "IN_5_P$6") (pintype "input"))
      (node (ref "CMP29") (pin "P$6") (pinfunction "IN_5_P$6") (pintype "input"))
    )
    (net (code "70") (name "H_6") (class "Default")
      (node (ref "CMP19") (pin "P$7") (pinfunction "OUT_6_P$7") (pintype "output"))
      (node (ref "CMP28") (pin "P$7") (pinfunction "IN_6_P$7") (pintype "input"))
      (node (ref "CMP29") (pin "P$7") (pinfunction "IN_6_P$7") (pintype "input"))
    )
    (net (code "71") (name "H_7") (class "Default")
      (node (ref "CMP19") (pin "P$8") (pinfunction "OUT_7_P$8") (pintype "output"))
      (node (ref "CMP28") (pin "P$8") (pinfunction "IN_7_P$8") (pintype "input"))
      (node (ref "CMP29") (pin "P$8") (pinfunction "IN_7_P$8") (pintype "input"))
    )
    (net (code "72") (name "H_8") (class "Default")
      (node (ref "CMP19") (pin "P$9") (pinfunction "OUT_8_P$9") (pintype "output"))
    )
    (net (code "73") (name "H_9") (class "Default")
      (node (ref "CMP19") (pin "P$10") (pinfunction "OUT_9_P$10") (pintype "output"))
    )
    (net (code "74") (name "H_10") (class "Default")
      (node (ref "CMP19") (pin "P$11") (pinfunction "OUT_10_P$11") (pintype "output"))
    )
    (net (code "75") (name "H_11") (class "Default")
      (node (ref "CMP19") (pin "P$12") (pinfunction "OUT_11_P$12") (pintype "output"))
    )
    (net (code "76") (name "H_12") (class "Default")
      (node (ref "CMP19") (pin "P$13") (pinfunction "OUT_12_P$13") (pintype "output"))
    )
    (net (code "77") (name "H_13") (class "Default")
      (node (ref "CMP19") (pin "P$14") (pinfunction "OUT_13_P$14") (pintype "output"))
    )
    (net (code "78") (name "H_14") (class "Default")
      (node (ref "CMP19") (pin "P$15") (pinfunction "OUT_14_P$15") (pintype "output"))
    )
    (net (code "79") (name "H_15") (class "Default")
      (node (ref "CMP19") (pin "P$16") (pinfunction "OUT_15_P$16") (pintype "output"))
    )
    (net (code "80") (name "H_ADDER0") (class "Default")
      (node (ref "CMP22") (pin "P$1") (pinfunction "OUT_0_P$1") (pintype "output"))
      (node (ref "CMP29") (pin "P$1") (pinfunction "IN_0_P$1") (pintype "input"))
    )
    (net (code "81") (name "H_ADDER1") (class "Default")
      (node (ref "CMP22") (pin "P$2") (pinfunction "OUT_1_P$2") (pintype "output"))
      (node (ref "CMP29") (pin "P$2") (pinfunction "IN_1_P$2") (pintype "input"))
    )
    (net (code "82") (name "H_ADDER2") (class "Default")
      (node (ref "CMP22") (pin "P$3") (pinfunction "OUT_2_P$3") (pintype "output"))
      (node (ref "CMP29") (pin "P$3") (pinfunction "IN_2_P$3") (pintype "input"))
    )
    (net (code "83") (name "H_ADDER3") (class "Default")
      (node (ref "CMP22") (pin "P$4") (pinfunction "OUT_3_P$4") (pintype "output"))
      (node (ref "CMP29") (pin "P$4") (pinfunction "IN_3_P$4") (pintype "input"))
    )
    (net (code "84") (name "H_ADDER4") (class "Default")
      (node (ref "CMP22") (pin "P$5") (pinfunction "OUT_4_P$5") (pintype "output"))
      (node (ref "CMP29") (pin "P$5") (pinfunction "IN_4_P$5") (pintype "input"))
    )
    (net (code "85") (name "H_ADDER5") (class "Default")
      (node (ref "CMP22") (pin "P$6") (pinfunction "OUT_5_P$6") (pintype "output"))
    )
    (net (code "86") (name "H_ADDER6") (class "Default")
      (node (ref "CMP22") (pin "P$7") (pinfunction "OUT_6_P$7") (pintype "output"))
    )
    (net (code "87") (name "H_ADDER7") (class "Default")
      (node (ref "CMP22") (pin "P$8") (pinfunction "OUT_7_P$8") (pintype "output"))
    )
    (net (code "88") (name "H_ADDER8") (class "Default")
      (node (ref "CMP22") (pin "P$9") (pinfunction "OUT_8_P$9") (pintype "output"))
    )
    (net (code "89") (name "H_ADDER9") (class "Default")
      (node (ref "CMP22") (pin "P$10") (pinfunction "OUT_9_P$10") (pintype "output"))
    )
    (net (code "90") (name "H_ADDER10") (class "Default")
      (node (ref "CMP22") (pin "P$11") (pinfunction "OUT_10_P$11") (pintype "output"))
    )
    (net (code "91") (name "H_ADDER11") (class "Default")
      (node (ref "CMP22") (pin "P$12") (pinfunction "OUT_11_P$12") (pintype "output"))
    )
    (net (code "92") (name "H_ADDER12") (class "Default")
      (node (ref "CMP22") (pin "P$13") (pinfunction "OUT_12_P$13") (pintype "output"))
    )
    (net (code "93") (name "H_ADDER13") (class "Default")
      (node (ref "CMP22") (pin "P$14") (pinfunction "OUT_13_P$14") (pintype "output"))
    )
    (net (code "94") (name "H_ADDER14") (class "Default")
      (node (ref "CMP22") (pin "P$15") (pinfunction "OUT_14_P$15") (pintype "output"))
    )
    (net (code "95") (name "H_ADDER15") (class "Default")
      (node (ref "CMP22") (pin "P$16") (pinfunction "OUT_15_P$16") (pintype "output"))
    )
    (net (code "96") (name "H_COUNT_DOWN__SHIFT") (class "Default")
      (node (ref "CMP6") (pin "C_IN") (pinfunction "C_IN_C_IN") (pintype "input"))
      (node (ref "CMP6") (pin "INV_B") (pinfunction "INV_B_INV_B") (pintype "input"))
      (node (ref "CMP9") (pin "P$1") (pinfunction "OUT_0_P$1") (pintype "output"))
    )
    (net (code "97") (name "H_SHIFT_UPDATE_DATA") (class "Default")
      (node (ref "CMP2") (pin "PORT1") (pinfunction "PORT1_PORT1") (pintype "input"))
      (node (ref "CMP29") (pin "INPUT") (pinfunction "OUT_INPUT") (pintype "output"))
    )
    (net (code "98") (name "NEXT_ADDR_MUX_ADD2") (class "Default")
      (node (ref "CMP14") (pin "P$9") (pinfunction "OUT_8_P$9") (pintype "output"))
      (node (ref "CMP56") (pin "EN1") (pinfunction "EN1_EN1") (pintype "input"))
    )
    (net (code "99") (name "NEXT_ADDR_MUX_PC") (class "Default")
      (node (ref "CMP14") (pin "P$7") (pinfunction "OUT_6_P$7") (pintype "output"))
      (node (ref "CMP56") (pin "EN3") (pinfunction "EN3_EN3") (pintype "input"))
    )
    (net (code "100") (name "NEXT_ADDR_MUX_READ_WORD") (class "Default")
      (node (ref "CMP14") (pin "P$8") (pinfunction "OUT_7_P$8") (pintype "output"))
      (node (ref "CMP56") (pin "EN2") (pinfunction "EN2_EN2") (pintype "input"))
    )
    (net (code "101") (name "NEXT_ADDR_MUX_RI") (class "Default")
      (node (ref "CMP14") (pin "P$10") (pinfunction "OUT_9_P$10") (pintype "output"))
      (node (ref "CMP56") (pin "EN0") (pinfunction "EN0_EN0") (pintype "input"))
    )
    (net (code "102") (name "NEXT_H_MUX") (class "Default")
      (node (ref "CMP2") (pin "PORTOUT") (pinfunction "OUTPUT_PORTOUT") (pintype "output"))
      (node (ref "CMP41") (pin "INPUT") (pinfunction "IN_INPUT") (pintype "input"))
    )
    (net (code "103") (name "NEXT_H_MUX_A") (class "Default")
      (node (ref "CMP1") (pin "PORTOUT") (pinfunction "OUTPUT_PORTOUT") (pintype "output"))
      (node (ref "CMP2") (pin "PORT2") (pinfunction "PORT2_PORT2") (pintype "input"))
    )
    (net (code "104") (name "NEXT_H_MUX_A_ABS_MSB") (class "Default")
      (node (ref "CMP1") (pin "EN1") (pinfunction "EN1_EN1") (pintype "input"))
      (node (ref "CMP9") (pin "P$11") (pinfunction "OUT_10_P$11") (pintype "output"))
    )
    (net (code "105") (name "NEXT_H_MUX_A_ADD2") (class "Default")
      (node (ref "CMP1") (pin "EN0") (pinfunction "EN0_EN0") (pintype "input"))
      (node (ref "CMP9") (pin "P$12") (pinfunction "OUT_11_P$12") (pintype "output"))
    )
    (net (code "106") (name "NEXT_H_MUX_A_R1") (class "Default")
      (node (ref "CMP1") (pin "EN2") (pinfunction "EN2_EN2") (pintype "input"))
      (node (ref "CMP9") (pin "P$10") (pinfunction "OUT_9_P$10") (pintype "output"))
    )
    (net (code "107") (name "NEXT_H_MUX_A_SXT_RD_DATA") (class "Default")
      (node (ref "CMP1") (pin "EN3") (pinfunction "EN3_EN3") (pintype "input"))
      (node (ref "CMP9") (pin "P$9") (pinfunction "OUT_8_P$9") (pintype "output"))
    )
    (net (code "108") (name "NEXT_H_MUX_B_A") (class "Default")
      (node (ref "CMP2") (pin "EN2") (pinfunction "EN2_EN2") (pintype "input"))
      (node (ref "CMP9") (pin "P$3") (pinfunction "OUT_2_P$3") (pintype "output"))
    )
    (net (code "109") (name "NEXT_H_MUX_B_HOLD") (class "Default")
      (node (ref "CMP2") (pin "EN3") (pinfunction "EN3_EN3") (pintype "input"))
      (node (ref "CMP9") (pin "P$2") (pinfunction "OUT_1_P$2") (pintype "output"))
    )
    (net (code "110") (name "NEXT_H_MUX_B_SHIFT_REG_VAL") (class "Default")
      (node (ref "CMP2") (pin "EN0") (pinfunction "EN0_EN0") (pintype "input"))
      (node (ref "CMP9") (pin "P$4") (pinfunction "OUT_3_P$4") (pintype "output"))
    )
    (net (code "111") (name "NEXT_H_MUX_B_SHIFT_UPDATE") (class "Default")
      (node (ref "CMP2") (pin "EN1") (pinfunction "EN1_EN1") (pintype "input"))
      (node (ref "CMP9") (pin "P$5") (pinfunction "OUT_4_P$5") (pintype "output"))
    )
    (net (code "112") (name "NEXT_PC_MUX_ADD2") (class "Default")
      (node (ref "CMP14") (pin "P$5") (pinfunction "OUT_4_P$5") (pintype "output"))
      (node (ref "CMP35") (pin "EN1") (pinfunction "EN1_EN1") (pintype "input"))
    )
    (net (code "113") (name "NEXT_PC_MUX_HOLD") (class "Default")
      (node (ref "CMP14") (pin "P$3") (pinfunction "OUT_2_P$3") (pintype "output"))
      (node (ref "CMP35") (pin "EN3") (pinfunction "EN3_EN3") (pintype "input"))
    )
    (net (code "114") (name "NEXT_PC_MUX_H_AND_DATA") (class "Default")
      (node (ref "CMP14") (pin "P$4") (pinfunction "OUT_3_P$4") (pintype "output"))
      (node (ref "CMP35") (pin "EN2") (pinfunction "EN2_EN2") (pintype "input"))
    )
    (net (code "115") (name "NEXT_SP_MUX_ADD2") (class "Default")
      (node (ref "CMP14") (pin "P$11") (pinfunction "OUT_10_P$11") (pintype "output"))
      (node (ref "CMP51") (pin "EN1") (pinfunction "EN1_EN1") (pintype "input"))
    )
    (net (code "116") (name "NEXT_SP_MUX_HOLD") (class "Default")
      (node (ref "CMP14") (pin "P$12") (pinfunction "OUT_11_P$12") (pintype "output"))
      (node (ref "CMP51") (pin "EN0") (pinfunction "EN0_EN0") (pintype "input"))
    )
    (net (code "117") (name "NEXT_WR_DATA_MUX_PC_RA_LSB") (class "Default")
      (node (ref "CMP13") (pin "EN2") (pinfunction "EN2_EN2") (pintype "input"))
      (node (ref "CMP9") (pin "P$7") (pinfunction "OUT_6_P$7") (pintype "output"))
    )
    (net (code "118") (name "NEXT_WR_DATA_MUX_PC_RA_MSB") (class "Default")
      (node (ref "CMP13") (pin "EN1") (pinfunction "EN1_EN1") (pintype "input"))
      (node (ref "CMP9") (pin "P$8") (pinfunction "OUT_7_P$8") (pintype "output"))
    )
    (net (code "119") (name "NEXT_WR_DATA_MUX_PS") (class "Default")
      (node (ref "CMP13") (pin "EN3") (pinfunction "EN3_EN3") (pintype "input"))
      (node (ref "CMP9") (pin "P$6") (pinfunction "OUT_5_P$6") (pintype "output"))
    )
    (net (code "120") (name "NEXT_WR_DATA_WIDE_MUX_PC") (class "Default")
      (node (ref "CMP12") (pin "EN1") (pinfunction "EN1_EN1") (pintype "input"))
      (node (ref "CMP9") (pin "P$13") (pinfunction "OUT_12_P$13") (pintype "output"))
    )
    (net (code "121") (name "NEXT_WR_DATA_WIDE_MUX_RA") (class "Default")
      (node (ref "CMP12") (pin "EN0") (pinfunction "EN0_EN0") (pintype "input"))
      (node (ref "CMP9") (pin "P$14") (pinfunction "OUT_13_P$14") (pintype "output"))
    )
    (net (code "122") (name "Net-(CMP3-IN)") (class "Default")
      (node (ref "CMP3") (pin "P$1") (pinfunction "IN_P$1") (pintype "input"))
      (node (ref "CMP33") (pin "OUT_A") (pinfunction "A_OUT_A") (pintype "output"))
    )
    (net (code "123") (name "Net-(CMP4-IN_1)") (class "Default")
      (node (ref "CMP4") (pin "P$10") (pinfunction "IN_9_P$10") (pintype "input"))
      (node (ref "CMP4") (pin "P$11") (pinfunction "IN_10_P$11") (pintype "input"))
      (node (ref "CMP4") (pin "P$12") (pinfunction "IN_11_P$12") (pintype "input"))
      (node (ref "CMP4") (pin "P$13") (pinfunction "IN_12_P$13") (pintype "input"))
      (node (ref "CMP4") (pin "P$14") (pinfunction "IN_13_P$14") (pintype "input"))
      (node (ref "CMP4") (pin "P$15") (pinfunction "IN_14_P$15") (pintype "input"))
      (node (ref "CMP4") (pin "P$16") (pinfunction "IN_15_P$16") (pintype "input"))
      (node (ref "CMP4") (pin "P$2") (pinfunction "IN_1_P$2") (pintype "input"))
      (node (ref "CMP4") (pin "P$3") (pinfunction "IN_2_P$3") (pintype "input"))
      (node (ref "CMP4") (pin "P$4") (pinfunction "IN_3_P$4") (pintype "input"))
      (node (ref "CMP4") (pin "P$5") (pinfunction "IN_4_P$5") (pintype "input"))
      (node (ref "CMP4") (pin "P$6") (pinfunction "IN_5_P$6") (pintype "input"))
      (node (ref "CMP4") (pin "P$7") (pinfunction "IN_6_P$7") (pintype "input"))
      (node (ref "CMP4") (pin "P$8") (pinfunction "IN_7_P$8") (pintype "input"))
      (node (ref "CMP4") (pin "P$9") (pinfunction "IN_8_P$9") (pintype "input"))
    )
    (net (code "124") (name "Net-(CMP4-OUT)") (class "Default")
      (node (ref "CMP4") (pin "INPUT") (pinfunction "OUT_INPUT") (pintype "output"))
      (node (ref "CMP6") (pin "B") (pinfunction "B_B") (pintype "input"))
    )
    (net (code "125") (name "Net-(CMP7-IN)") (class "Default")
      (node (ref "CMP6") (pin "DISP") (pinfunction "DISP_DISP") (pintype "output"))
      (node (ref "CMP7") (pin "P$1") (pinfunction "IN_P$1") (pintype "input"))
    )
    (net (code "126") (name "Net-(CMP12-OUTPUT)") (class "Default")
      (node (ref "CMP12") (pin "OUT") (pinfunction "OUTPUT_OUT") (pintype "output"))
      (node (ref "CMP8") (pin "SRC") (pinfunction "SRC_SRC") (pintype "input"))
    )
    (net (code "127") (name "Net-(CMP13-OUTPUT)") (class "Default")
      (node (ref "CMP13") (pin "PORTOUT") (pinfunction "OUTPUT_PORTOUT") (pintype "output"))
      (node (ref "CMP20") (pin "INPUT") (pinfunction "IN_INPUT") (pintype "input"))
    )
    (net (code "128") (name "Net-(CMP13-PadPORT1)") (class "Default")
      (node (ref "CMP13") (pin "PORT1") (pinfunction "PORT1_PORT1") (pintype "input"))
      (node (ref "CMP8") (pin "MSB_1") (pinfunction "MSB_1_MSB_1") (pintype "output"))
    )
    (net (code "129") (name "Net-(CMP13-PadPORT2)") (class "Default")
      (node (ref "CMP13") (pin "PORT2") (pinfunction "PORT2_PORT2") (pintype "input"))
      (node (ref "CMP8") (pin "LSB_1") (pinfunction "LSB_1_LSB_1") (pintype "output"))
    )
    (net (code "130") (name "Net-(CMP15-PadSRC)") (class "Default")
      (node (ref "CMP15") (pin "SRC") (pinfunction "SRC_SRC") (pintype "input"))
      (node (ref "CMP38") (pin "OUT") (pinfunction "OUT_OUT") (pintype "output"))
    )
    (net (code "131") (name "Net-(CMP16-B)") (class "Default")
      (node (ref "CMP16") (pin "OUTB") (pinfunction "B_OUTB") (pintype "output"))
      (node (ref "CMP17") (pin "INPUT") (pinfunction "INPUT_INPUT") (pintype "input"))
    )
    (net (code "132") (name "Net-(CMP16-IN)") (class "Default")
      (node (ref "CMP10") (pin "1") (pinfunction "1_1") (pintype "output"))
      (node (ref "CMP16") (pin "INPUT") (pinfunction "IN_INPUT") (pintype "input"))
    )
    (net (code "133") (name "Net-(CMP18-IN)") (class "Default")
      (node (ref "CMP18") (pin "P$1") (pinfunction "IN_P$1") (pintype "input"))
      (node (ref "CMP20") (pin "DISPLAY") (pinfunction "DSP_DISPLAY") (pintype "output"))
    )
    (net (code "134") (name "Net-(CMP23-IN)") (class "Default")
      (node (ref "CMP20") (pin "OUT") (pinfunction "OUT_OUT") (pintype "output"))
      (node (ref "CMP23") (pin "P$1") (pinfunction "IN_P$1") (pintype "input"))
    )
    (net (code "135") (name "Net-(CMP28-IN_10)") (class "Default")
      (node (ref "CMP28") (pin "P$10") (pinfunction "IN_9_P$10") (pintype "input"))
      (node (ref "CMP28") (pin "P$11") (pinfunction "IN_10_P$11") (pintype "input"))
      (node (ref "CMP28") (pin "P$12") (pinfunction "IN_11_P$12") (pintype "input"))
      (node (ref "CMP28") (pin "P$13") (pinfunction "IN_12_P$13") (pintype "input"))
      (node (ref "CMP28") (pin "P$14") (pinfunction "IN_13_P$14") (pintype "input"))
      (node (ref "CMP28") (pin "P$15") (pinfunction "IN_14_P$15") (pintype "input"))
      (node (ref "CMP28") (pin "P$16") (pinfunction "IN_15_P$16") (pintype "input"))
      (node (ref "CMP28") (pin "P$9") (pinfunction "IN_8_P$9") (pintype "input"))
    )
    (net (code "136") (name "Net-(CMP30-IN_0)") (class "Default")
      (node (ref "CMP30") (pin "P$1") (pinfunction "IN_0_P$1") (pintype "input"))
      (node (ref "CMP30") (pin "P$10") (pinfunction "IN_9_P$10") (pintype "input"))
      (node (ref "CMP30") (pin "P$11") (pinfunction "IN_10_P$11") (pintype "input"))
      (node (ref "CMP30") (pin "P$12") (pinfunction "IN_11_P$12") (pintype "input"))
      (node (ref "CMP30") (pin "P$13") (pinfunction "IN_12_P$13") (pintype "input"))
      (node (ref "CMP30") (pin "P$14") (pinfunction "IN_13_P$14") (pintype "input"))
      (node (ref "CMP30") (pin "P$15") (pinfunction "IN_14_P$15") (pintype "input"))
      (node (ref "CMP30") (pin "P$16") (pinfunction "IN_15_P$16") (pintype "input"))
      (node (ref "CMP30") (pin "P$2") (pinfunction "IN_1_P$2") (pintype "input"))
      (node (ref "CMP30") (pin "P$3") (pinfunction "IN_2_P$3") (pintype "input"))
      (node (ref "CMP30") (pin "P$4") (pinfunction "IN_3_P$4") (pintype "input"))
      (node (ref "CMP30") (pin "P$5") (pinfunction "IN_4_P$5") (pintype "input"))
      (node (ref "CMP30") (pin "P$6") (pinfunction "IN_5_P$6") (pintype "input"))
      (node (ref "CMP30") (pin "P$7") (pinfunction "IN_6_P$7") (pintype "input"))
      (node (ref "CMP30") (pin "P$8") (pinfunction "IN_7_P$8") (pintype "input"))
      (node (ref "CMP30") (pin "P$9") (pinfunction "IN_8_P$9") (pintype "input"))
    )
    (net (code "137") (name "Net-(CMP30-OUT)") (class "Default")
      (node (ref "CMP13") (pin "PORT0") (pinfunction "PORT0_PORT0") (pintype "input"))
      (node (ref "CMP30") (pin "INPUT") (pinfunction "OUT_INPUT") (pintype "output"))
    )
    (net (code "138") (name "Net-(CMP32-IN)") (class "Default")
      (node (ref "CMP32") (pin "P$1") (pinfunction "IN_P$1") (pintype "input"))
      (node (ref "U$1") (pin "MSB_1") (pinfunction "MSB_1_MSB_1") (pintype "input"))
    )
    (net (code "139") (name "Net-(CMP33-B)") (class "Default")
      (node (ref "CMP33") (pin "OUTB") (pinfunction "B_OUTB") (pintype "output"))
      (node (ref "U$1") (pin "SRC") (pinfunction "WORD_SRC") (pintype "output"))
    )
    (net (code "140") (name "Net-(CMP35-OUTPUT)") (class "Default")
      (node (ref "CMP35") (pin "PORTOUT") (pinfunction "OUTPUT_PORTOUT") (pintype "output"))
      (node (ref "CMP45") (pin "INPUT") (pinfunction "IN_INPUT") (pintype "input"))
    )
    (net (code "141") (name "Net-(CMP38-DSP)") (class "Default")
      (node (ref "CMP38") (pin "DISPLAY") (pinfunction "DSP_DISPLAY") (pintype "output"))
      (node (ref "CMP39") (pin "P$1") (pinfunction "IN_P$1") (pintype "input"))
    )
    (net (code "142") (name "Net-(CMP38-IN)") (class "Default")
      (node (ref "CMP38") (pin "INPUT") (pinfunction "IN_INPUT") (pintype "input"))
      (node (ref "CMP45") (pin "OUT_A") (pinfunction "A_OUT_A") (pintype "output"))
    )
    (net (code "143") (name "Net-(CMP42-IN)") (class "Default")
      (node (ref "CMP15") (pin "1") (pinfunction "1_1") (pintype "output"))
      (node (ref "CMP42") (pin "P$1") (pinfunction "IN_P$1") (pintype "input"))
    )
    (net (code "144") (name "Net-(CMP50-IN_0)") (class "Default")
      (node (ref "CMP50") (pin "P$1") (pinfunction "IN_0_P$1") (pintype "input"))
      (node (ref "CMP50") (pin "P$2") (pinfunction "IN_1_P$2") (pintype "input"))
    )
    (net (code "145") (name "Net-(CMP50-IN_10)") (class "Default")
      (node (ref "CMP50") (pin "P$10") (pinfunction "IN_9_P$10") (pintype "input"))
      (node (ref "CMP50") (pin "P$11") (pinfunction "IN_10_P$11") (pintype "input"))
      (node (ref "CMP50") (pin "P$12") (pinfunction "IN_11_P$12") (pintype "input"))
      (node (ref "CMP50") (pin "P$13") (pinfunction "IN_12_P$13") (pintype "input"))
      (node (ref "CMP50") (pin "P$14") (pinfunction "IN_13_P$14") (pintype "input"))
      (node (ref "CMP50") (pin "P$15") (pinfunction "IN_14_P$15") (pintype "input"))
      (node (ref "CMP50") (pin "P$16") (pinfunction "IN_15_P$16") (pintype "input"))
      (node (ref "CMP50") (pin "P$5") (pinfunction "IN_4_P$5") (pintype "input"))
      (node (ref "CMP50") (pin "P$6") (pinfunction "IN_5_P$6") (pintype "input"))
      (node (ref "CMP50") (pin "P$7") (pinfunction "IN_6_P$7") (pintype "input"))
      (node (ref "CMP50") (pin "P$8") (pinfunction "IN_7_P$8") (pintype "input"))
      (node (ref "CMP50") (pin "P$9") (pinfunction "IN_8_P$9") (pintype "input"))
    )
    (net (code "146") (name "Net-(CMP51-OUTPUT)") (class "Default")
      (node (ref "CMP51") (pin "OUT") (pinfunction "OUTPUT_OUT") (pintype "output"))
      (node (ref "CMP52") (pin "INPUT") (pinfunction "IN_INPUT") (pintype "input"))
    )
    (net (code "147") (name "Net-(CMP52-DSP)") (class "Default")
      (node (ref "CMP52") (pin "DISPLAY") (pinfunction "DSP_DISPLAY") (pintype "output"))
      (node (ref "CMP53") (pin "P$1") (pinfunction "IN_P$1") (pintype "input"))
    )
    (net (code "148") (name "Net-(CMP54-IN)") (class "Default")
      (node (ref "CMP52") (pin "OUT") (pinfunction "OUT_OUT") (pintype "output"))
      (node (ref "CMP54") (pin "INPUT") (pinfunction "IN_INPUT") (pintype "input"))
    )
    (net (code "149") (name "Net-(CMP56-OUTPUT)") (class "Default")
      (node (ref "CMP56") (pin "PORTOUT") (pinfunction "OUTPUT_PORTOUT") (pintype "output"))
      (node (ref "CMP57") (pin "INPUT") (pinfunction "IN_INPUT") (pintype "input"))
    )
    (net (code "150") (name "Net-(CMP57-DSP)") (class "Default")
      (node (ref "CMP57") (pin "DISPLAY") (pinfunction "DSP_DISPLAY") (pintype "output"))
      (node (ref "CMP58") (pin "P$1") (pinfunction "IN_P$1") (pintype "input"))
    )
    (net (code "151") (name "Net-(CMP59-IN)") (class "Default")
      (node (ref "CMP57") (pin "OUT") (pinfunction "OUT_OUT") (pintype "output"))
      (node (ref "CMP59") (pin "P$1") (pinfunction "IN_P$1") (pintype "input"))
    )
    (net (code "152") (name "OPCODE_IS_STACK_REL_GROUP_N") (class "Default")
      (node (ref "CMP31") (pin "P$1") (pinfunction "1_P$1") (pintype "input"))
      (node (ref "CMP9") (pin "P$15") (pinfunction "OUT_14_P$15") (pintype "output"))
    )
    (net (code "153") (name "REG_H") (class "Default")
      (node (ref "CMP34") (pin "SRC") (pinfunction "SRC_SRC") (pintype "input"))
      (node (ref "CMP41") (pin "OUT") (pinfunction "OUT_OUT") (pintype "output"))
    )
    (net (code "154") (name "REG_R1_ROTATE") (class "Default")
      (node (ref "CMP1") (pin "PORT2") (pinfunction "PORT2_PORT2") (pintype "input"))
      (node (ref "CMP5") (pin "P$2") (pinfunction "OUT_P$2") (pintype "output"))
    )
    (net (code "155") (name "REG_SP_A") (class "Default")
      (node (ref "CMP51") (pin "PORT0") (pinfunction "PORT0_PORT0") (pintype "input"))
      (node (ref "CMP54") (pin "OUT_A") (pinfunction "A_OUT_A") (pintype "output"))
    )
    (net (code "156") (name "REG_SP_B") (class "Default")
      (node (ref "CMP54") (pin "OUTB") (pinfunction "B_OUTB") (pintype "output"))
      (node (ref "CMP55") (pin "P$1") (pinfunction "IN_P$1") (pintype "input"))
    )
    (net (code "157") (name "SHIFT_REG_VALUE") (class "Default")
      (node (ref "CMP2") (pin "PORT0") (pinfunction "PORT0_PORT0") (pintype "input"))
      (node (ref "CMP28") (pin "INPUT") (pinfunction "OUT_INPUT") (pintype "output"))
    )
    (net (code "158") (name "SIGN_EXTEND_READ_DATA") (class "Default")
      (node (ref "CMP1") (pin "PORT3") (pinfunction "PORT3_PORT3") (pintype "input"))
      (node (ref "CMP27") (pin "INPUT") (pinfunction "OUT_INPUT") (pintype "output"))
    )
    (net (code "159") (name "SIGN_EXTEND_VAL") (class "Default")
      (node (ref "CMP27") (pin "P$10") (pinfunction "IN_9_P$10") (pintype "input"))
      (node (ref "CMP27") (pin "P$11") (pinfunction "IN_10_P$11") (pintype "input"))
      (node (ref "CMP27") (pin "P$12") (pinfunction "IN_11_P$12") (pintype "input"))
      (node (ref "CMP27") (pin "P$13") (pinfunction "IN_12_P$13") (pintype "input"))
      (node (ref "CMP27") (pin "P$14") (pinfunction "IN_13_P$14") (pintype "input"))
      (node (ref "CMP27") (pin "P$15") (pinfunction "IN_14_P$15") (pintype "input"))
      (node (ref "CMP27") (pin "P$16") (pinfunction "IN_15_P$16") (pintype "input"))
      (node (ref "CMP27") (pin "P$9") (pinfunction "IN_8_P$9") (pintype "input"))
      (node (ref "CMP31") (pin "OUT_P") (pinfunction "P_OUT_P") (pintype "output"))
    )
    (net (code "160") (name "TRAP_STATE_7") (class "Default")
      (node (ref "CMP14") (pin "P$6") (pinfunction "OUT_5_P$6") (pintype "output"))
      (node (ref "CMP35") (pin "EN0") (pinfunction "EN0_EN0") (pintype "input"))
    )
    (net (code "161") (name "VECTOR_CODE_0") (class "Default")
      (node (ref "CMP14") (pin "P$2") (pinfunction "OUT_1_P$2") (pintype "output"))
      (node (ref "CMP50") (pin "P$3") (pinfunction "IN_2_P$3") (pintype "input"))
    )
    (net (code "162") (name "VECTOR_CODE_1") (class "Default")
      (node (ref "CMP14") (pin "P$1") (pinfunction "OUT_0_P$1") (pintype "output"))
      (node (ref "CMP50") (pin "P$4") (pinfunction "IN_3_P$4") (pintype "input"))
    )
    (net (code "163") (name "VECTOR_VALUE") (class "Default")
      (node (ref "CMP35") (pin "PORT0") (pinfunction "PORT0_PORT0") (pintype "input"))
      (node (ref "CMP50") (pin "INPUT") (pinfunction "OUT_INPUT") (pintype "output"))
    )
    (net (code "164") (name "ZXT_READ_DATA_0") (class "Default")
      (node (ref "CMP21") (pin "P$1") (pinfunction "OUT_0_P$1") (pintype "output"))
      (node (ref "CMP27") (pin "P$1") (pinfunction "IN_0_P$1") (pintype "input"))
    )
    (net (code "165") (name "ZXT_READ_DATA_1") (class "Default")
      (node (ref "CMP21") (pin "P$2") (pinfunction "OUT_1_P$2") (pintype "output"))
      (node (ref "CMP27") (pin "P$2") (pinfunction "IN_1_P$2") (pintype "input"))
    )
    (net (code "166") (name "ZXT_READ_DATA_2") (class "Default")
      (node (ref "CMP21") (pin "P$3") (pinfunction "OUT_2_P$3") (pintype "output"))
      (node (ref "CMP27") (pin "P$3") (pinfunction "IN_2_P$3") (pintype "input"))
    )
    (net (code "167") (name "ZXT_READ_DATA_3") (class "Default")
      (node (ref "CMP21") (pin "P$4") (pinfunction "OUT_3_P$4") (pintype "output"))
      (node (ref "CMP27") (pin "P$4") (pinfunction "IN_3_P$4") (pintype "input"))
    )
    (net (code "168") (name "ZXT_READ_DATA_4") (class "Default")
      (node (ref "CMP21") (pin "P$5") (pinfunction "OUT_4_P$5") (pintype "output"))
      (node (ref "CMP27") (pin "P$5") (pinfunction "IN_4_P$5") (pintype "input"))
    )
    (net (code "169") (name "ZXT_READ_DATA_5") (class "Default")
      (node (ref "CMP21") (pin "P$6") (pinfunction "OUT_5_P$6") (pintype "output"))
      (node (ref "CMP27") (pin "P$6") (pinfunction "IN_5_P$6") (pintype "input"))
    )
    (net (code "170") (name "ZXT_READ_DATA_6") (class "Default")
      (node (ref "CMP21") (pin "P$7") (pinfunction "OUT_6_P$7") (pintype "output"))
      (node (ref "CMP27") (pin "P$7") (pinfunction "IN_6_P$7") (pintype "input"))
    )
    (net (code "171") (name "ZXT_READ_DATA_7") (class "Default")
      (node (ref "CMP21") (pin "P$8") (pinfunction "OUT_7_P$8") (pintype "output"))
      (node (ref "CMP27") (pin "P$8") (pinfunction "IN_7_P$8") (pintype "input"))
      (node (ref "CMP31") (pin "P$2") (pinfunction "2_P$2") (pintype "input"))
    )
    (net (code "172") (name "ZXT_READ_DATA_8") (class "Default")
      (node (ref "CMP21") (pin "P$9") (pinfunction "OUT_8_P$9") (pintype "output"))
    )
    (net (code "173") (name "ZXT_READ_DATA_9") (class "Default")
      (node (ref "CMP21") (pin "P$10") (pinfunction "OUT_9_P$10") (pintype "output"))
    )
    (net (code "174") (name "ZXT_READ_DATA_10") (class "Default")
      (node (ref "CMP21") (pin "P$11") (pinfunction "OUT_10_P$11") (pintype "output"))
    )
    (net (code "175") (name "ZXT_READ_DATA_11") (class "Default")
      (node (ref "CMP21") (pin "P$12") (pinfunction "OUT_11_P$12") (pintype "output"))
    )
    (net (code "176") (name "ZXT_READ_DATA_12") (class "Default")
      (node (ref "CMP21") (pin "P$13") (pinfunction "OUT_12_P$13") (pintype "output"))
    )
    (net (code "177") (name "ZXT_READ_DATA_13") (class "Default")
      (node (ref "CMP21") (pin "P$14") (pinfunction "OUT_13_P$14") (pintype "output"))
    )
    (net (code "178") (name "ZXT_READ_DATA_14") (class "Default")
      (node (ref "CMP21") (pin "P$15") (pinfunction "OUT_14_P$15") (pintype "output"))
    )
    (net (code "179") (name "ZXT_READ_DATA_15") (class "Default")
      (node (ref "CMP21") (pin "P$16") (pinfunction "OUT_15_P$16") (pintype "output"))
    )
    (net (code "180") (name "unconnected-(CMP3-OUT-PadP$2)") (class "Default")
      (node (ref "CMP3") (pin "P$2") (pinfunction "OUT_P$2") (pintype "output"))
    )
    (net (code "181") (name "unconnected-(CMP4-IN_0-PadP$1)") (class "Default")
      (node (ref "CMP4") (pin "P$1") (pinfunction "IN_0_P$1") (pintype "input"))
    )
    (net (code "182") (name "unconnected-(CMP5-IN-PadP$1)") (class "Default")
      (node (ref "CMP5") (pin "P$1") (pinfunction "IN_P$1") (pintype "input"))
    )
    (net (code "183") (name "unconnected-(CMP6-PadC_OUT)") (class "Default")
      (node (ref "CMP6") (pin "C_OUT") (pinfunction "C_OUT_C_OUT") (pintype "output"))
    )
    (net (code "184") (name "unconnected-(CMP8-PadLSB_2)") (class "Default")
      (node (ref "CMP8") (pin "LSB_2") (pinfunction "LSB_2_LSB_2") (pintype "output"))
    )
    (net (code "185") (name "unconnected-(CMP8-PadMSB_2)") (class "Default")
      (node (ref "CMP8") (pin "MSB_2") (pinfunction "MSB_2_MSB_2") (pintype "output"))
    )
    (net (code "186") (name "unconnected-(CMP8-PadMS_BIT)") (class "Default")
      (node (ref "CMP8") (pin "MS_BIT") (pinfunction "MS_BIT_MS_BIT") (pintype "output"))
    )
    (net (code "187") (name "unconnected-(CMP9-OUT_15-PadP$16)") (class "Default")
      (node (ref "CMP9") (pin "P$16") (pinfunction "OUT_15_P$16") (pintype "output"))
    )
    (net (code "188") (name "unconnected-(CMP10-PadSRC)") (class "Default")
      (node (ref "CMP10") (pin "SRC") (pinfunction "SRC_SRC") (pintype "input"))
    )
    (net (code "189") (name "unconnected-(CMP13-PadEN0)") (class "Default")
      (node (ref "CMP13") (pin "EN0") (pinfunction "EN0_EN0") (pintype "input"))
    )
    (net (code "190") (name "unconnected-(CMP14-OUT_12-PadP$13)") (class "Default")
      (node (ref "CMP14") (pin "P$13") (pinfunction "OUT_12_P$13") (pintype "output"))
    )
    (net (code "191") (name "unconnected-(CMP14-OUT_13-PadP$14)") (class "Default")
      (node (ref "CMP14") (pin "P$14") (pinfunction "OUT_13_P$14") (pintype "output"))
    )
    (net (code "192") (name "unconnected-(CMP14-OUT_14-PadP$15)") (class "Default")
      (node (ref "CMP14") (pin "P$15") (pinfunction "OUT_14_P$15") (pintype "output"))
    )
    (net (code "193") (name "unconnected-(CMP14-OUT_15-PadP$16)") (class "Default")
      (node (ref "CMP14") (pin "P$16") (pinfunction "OUT_15_P$16") (pintype "output"))
    )
    (net (code "194") (name "unconnected-(CMP15-Pad2)") (class "Default")
      (node (ref "CMP15") (pin "2") (pinfunction "2_2") (pintype "output"))
    )
    (net (code "195") (name "unconnected-(CMP17-OUT_8-PadP$9)") (class "Default")
      (node (ref "CMP17") (pin "P$9") (pinfunction "OUT_8_P$9") (pintype "output"))
    )
    (net (code "196") (name "unconnected-(CMP17-OUT_9-PadP$10)") (class "Default")
      (node (ref "CMP17") (pin "P$10") (pinfunction "OUT_9_P$10") (pintype "output"))
    )
    (net (code "197") (name "unconnected-(CMP17-OUT_10-PadP$11)") (class "Default")
      (node (ref "CMP17") (pin "P$11") (pinfunction "OUT_10_P$11") (pintype "output"))
    )
    (net (code "198") (name "unconnected-(CMP17-OUT_11-PadP$12)") (class "Default")
      (node (ref "CMP17") (pin "P$12") (pinfunction "OUT_11_P$12") (pintype "output"))
    )
    (net (code "199") (name "unconnected-(CMP17-OUT_12-PadP$13)") (class "Default")
      (node (ref "CMP17") (pin "P$13") (pinfunction "OUT_12_P$13") (pintype "output"))
    )
    (net (code "200") (name "unconnected-(CMP17-OUT_13-PadP$14)") (class "Default")
      (node (ref "CMP17") (pin "P$14") (pinfunction "OUT_13_P$14") (pintype "output"))
    )
    (net (code "201") (name "unconnected-(CMP17-OUT_14-PadP$15)") (class "Default")
      (node (ref "CMP17") (pin "P$15") (pinfunction "OUT_14_P$15") (pintype "output"))
    )
    (net (code "202") (name "unconnected-(CMP17-OUT_15-PadP$16)") (class "Default")
      (node (ref "CMP17") (pin "P$16") (pinfunction "OUT_15_P$16") (pintype "output"))
    )
    (net (code "203") (name "unconnected-(CMP23-OUT-PadP$2)") (class "Default")
      (node (ref "CMP23") (pin "P$2") (pinfunction "OUT_P$2") (pintype "output"))
    )
    (net (code "204") (name "unconnected-(CMP24-OUT_5-PadP$6)") (class "Default")
      (node (ref "CMP24") (pin "P$6") (pinfunction "OUT_5_P$6") (pintype "output"))
    )
    (net (code "205") (name "unconnected-(CMP24-OUT_6-PadP$7)") (class "Default")
      (node (ref "CMP24") (pin "P$7") (pinfunction "OUT_6_P$7") (pintype "output"))
    )
    (net (code "206") (name "unconnected-(CMP24-OUT_7-PadP$8)") (class "Default")
      (node (ref "CMP24") (pin "P$8") (pinfunction "OUT_7_P$8") (pintype "output"))
    )
    (net (code "207") (name "unconnected-(CMP24-OUT_8-PadP$9)") (class "Default")
      (node (ref "CMP24") (pin "P$9") (pinfunction "OUT_8_P$9") (pintype "output"))
    )
    (net (code "208") (name "unconnected-(CMP24-OUT_9-PadP$10)") (class "Default")
      (node (ref "CMP24") (pin "P$10") (pinfunction "OUT_9_P$10") (pintype "output"))
    )
    (net (code "209") (name "unconnected-(CMP24-OUT_10-PadP$11)") (class "Default")
      (node (ref "CMP24") (pin "P$11") (pinfunction "OUT_10_P$11") (pintype "output"))
    )
    (net (code "210") (name "unconnected-(CMP24-OUT_11-PadP$12)") (class "Default")
      (node (ref "CMP24") (pin "P$12") (pinfunction "OUT_11_P$12") (pintype "output"))
    )
    (net (code "211") (name "unconnected-(CMP24-OUT_12-PadP$13)") (class "Default")
      (node (ref "CMP24") (pin "P$13") (pinfunction "OUT_12_P$13") (pintype "output"))
    )
    (net (code "212") (name "unconnected-(CMP24-OUT_13-PadP$14)") (class "Default")
      (node (ref "CMP24") (pin "P$14") (pinfunction "OUT_13_P$14") (pintype "output"))
    )
    (net (code "213") (name "unconnected-(CMP24-OUT_14-PadP$15)") (class "Default")
      (node (ref "CMP24") (pin "P$15") (pinfunction "OUT_14_P$15") (pintype "output"))
    )
    (net (code "214") (name "unconnected-(CMP24-OUT_15-PadP$16)") (class "Default")
      (node (ref "CMP24") (pin "P$16") (pinfunction "OUT_15_P$16") (pintype "output"))
    )
    (net (code "215") (name "unconnected-(CMP25-IN-PadP$1)") (class "Default")
      (node (ref "CMP25") (pin "P$1") (pinfunction "IN_P$1") (pintype "input"))
    )
    (net (code "216") (name "unconnected-(CMP26-IN-PadP$1)") (class "Default")
      (node (ref "CMP26") (pin "P$1") (pinfunction "IN_P$1") (pintype "input"))
    )
    (net (code "217") (name "unconnected-(CMP31-N-PadOUT_M)") (class "Default")
      (node (ref "CMP31") (pin "OUT_M") (pinfunction "N_OUT_M") (pintype "output"))
    )
    (net (code "218") (name "unconnected-(CMP32-OUT-PadP$2)") (class "Default")
      (node (ref "CMP32") (pin "P$2") (pinfunction "OUT_P$2") (pintype "output"))
    )
    (net (code "219") (name "unconnected-(CMP42-OUT-PadP$2)") (class "Default")
      (node (ref "CMP42") (pin "P$2") (pinfunction "OUT_P$2") (pintype "output"))
    )
    (net (code "220") (name "unconnected-(CMP48-IN-PadP$1)") (class "Default")
      (node (ref "CMP48") (pin "P$1") (pinfunction "IN_P$1") (pintype "input"))
    )
    (net (code "221") (name "unconnected-(CMP55-OUT-PadP$2)") (class "Default")
      (node (ref "CMP55") (pin "P$2") (pinfunction "OUT_P$2") (pintype "output"))
    )
    (net (code "222") (name "unconnected-(CMP59-OUT-PadP$2)") (class "Default")
      (node (ref "CMP59") (pin "P$2") (pinfunction "OUT_P$2") (pintype "output"))
    )
    (net (code "223") (name "unconnected-(U$1-PadLSB_1)") (class "Default")
      (node (ref "U$1") (pin "LSB_1") (pinfunction "LSB_1_LSB_1") (pintype "input"))
    )
    (net (code "224") (name "unconnected-(U$1-PadLSB_2)") (class "Default")
      (node (ref "U$1") (pin "LSB_2") (pinfunction "LSB_2_LSB_2") (pintype "input"))
    )
    (net (code "225") (name "unconnected-(U$1-PadMSB_2)") (class "Default")
      (node (ref "U$1") (pin "MSB_2") (pinfunction "MSB_2_MSB_2") (pintype "input"))
    )
    (net (code "226") (name "unconnected-(U$1-PadMS_BIT)") (class "Default")
      (node (ref "U$1") (pin "MS_BIT") (pinfunction "MS_BIT_MS_BIT") (pintype "output"))
    )
  )
)
